# main_xml.net
KiCad netlist of a schematic drawn in EAGLE
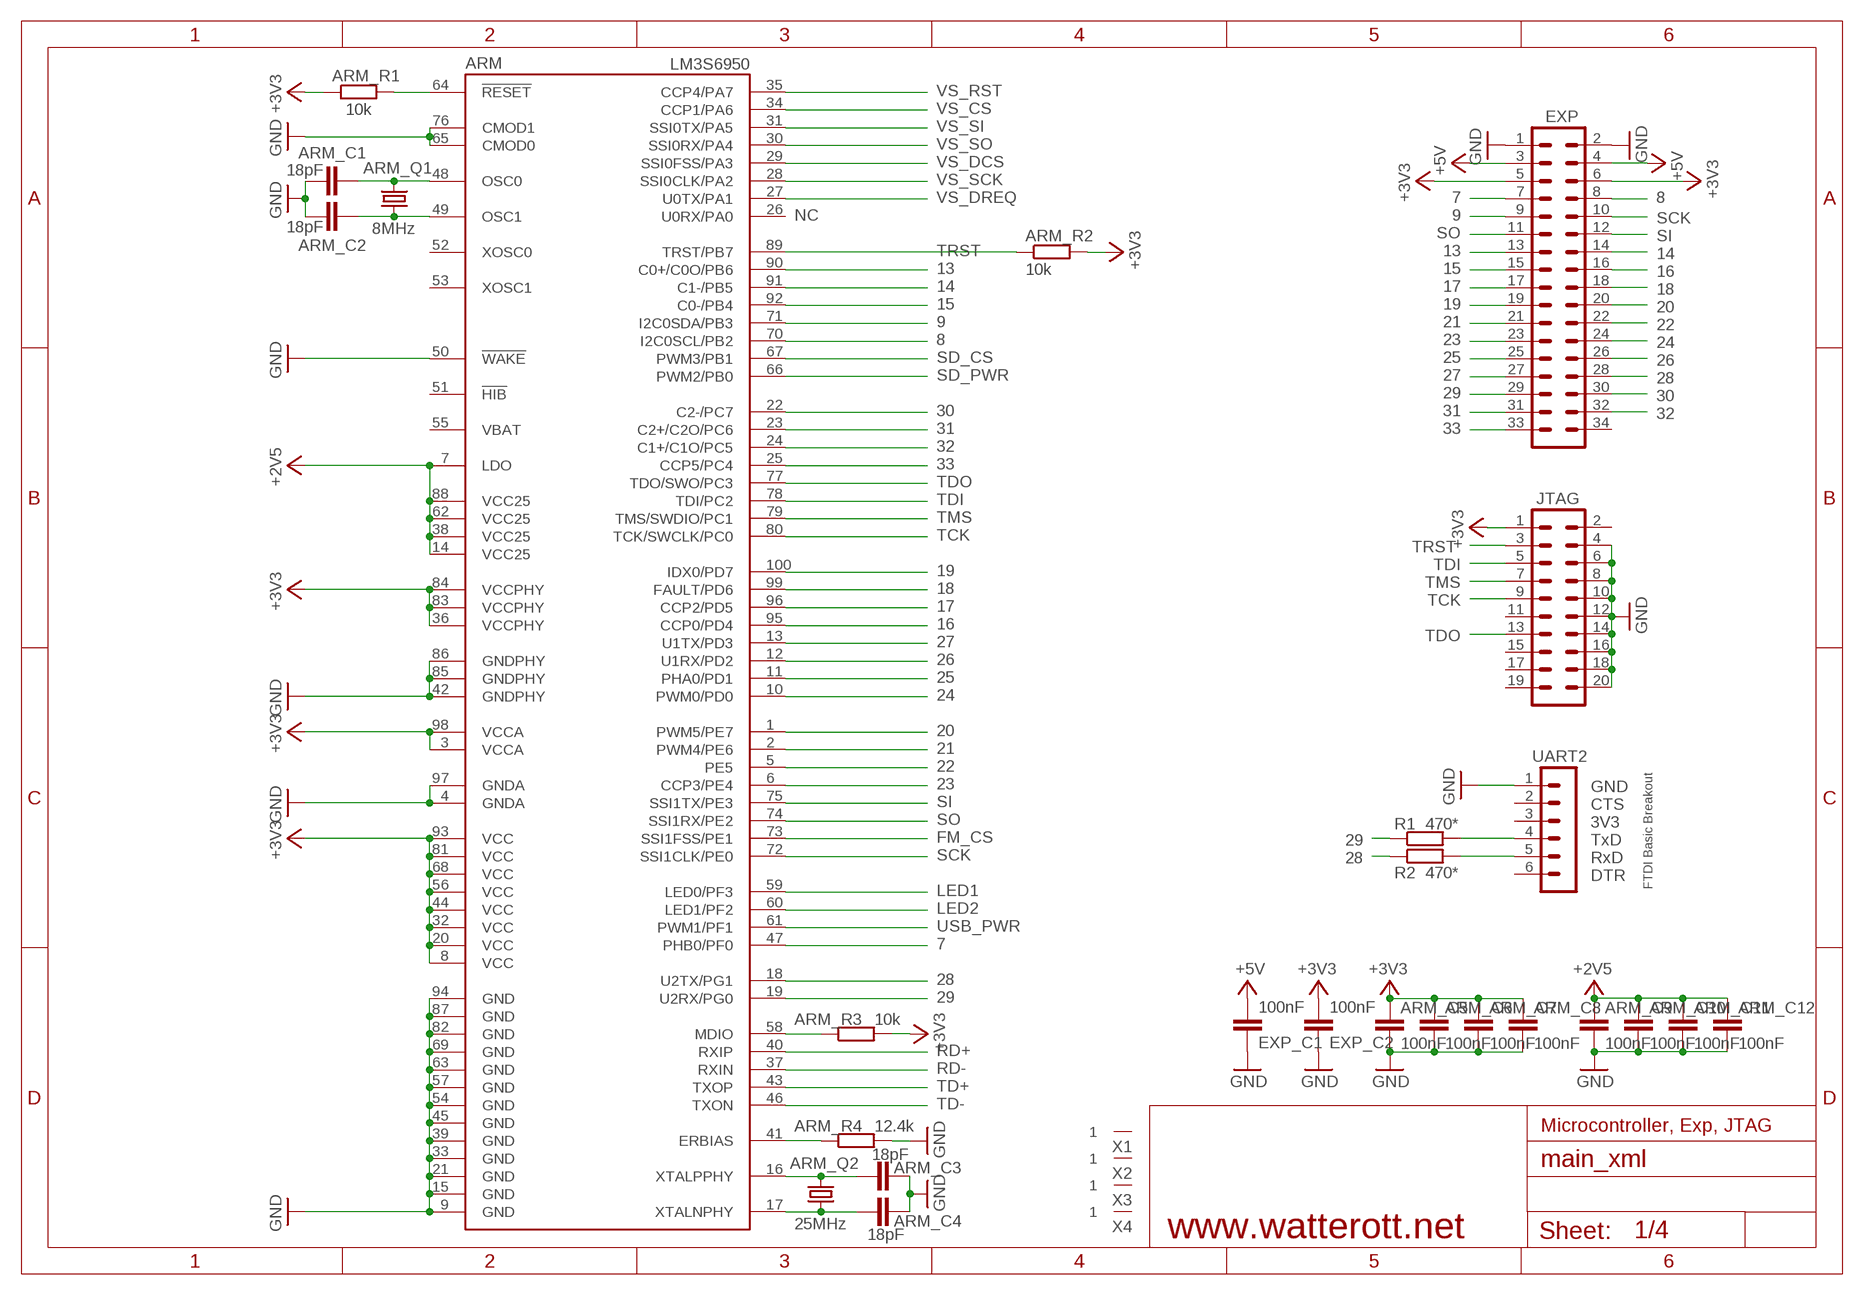
[diagram p0: schematic, sheet 1]
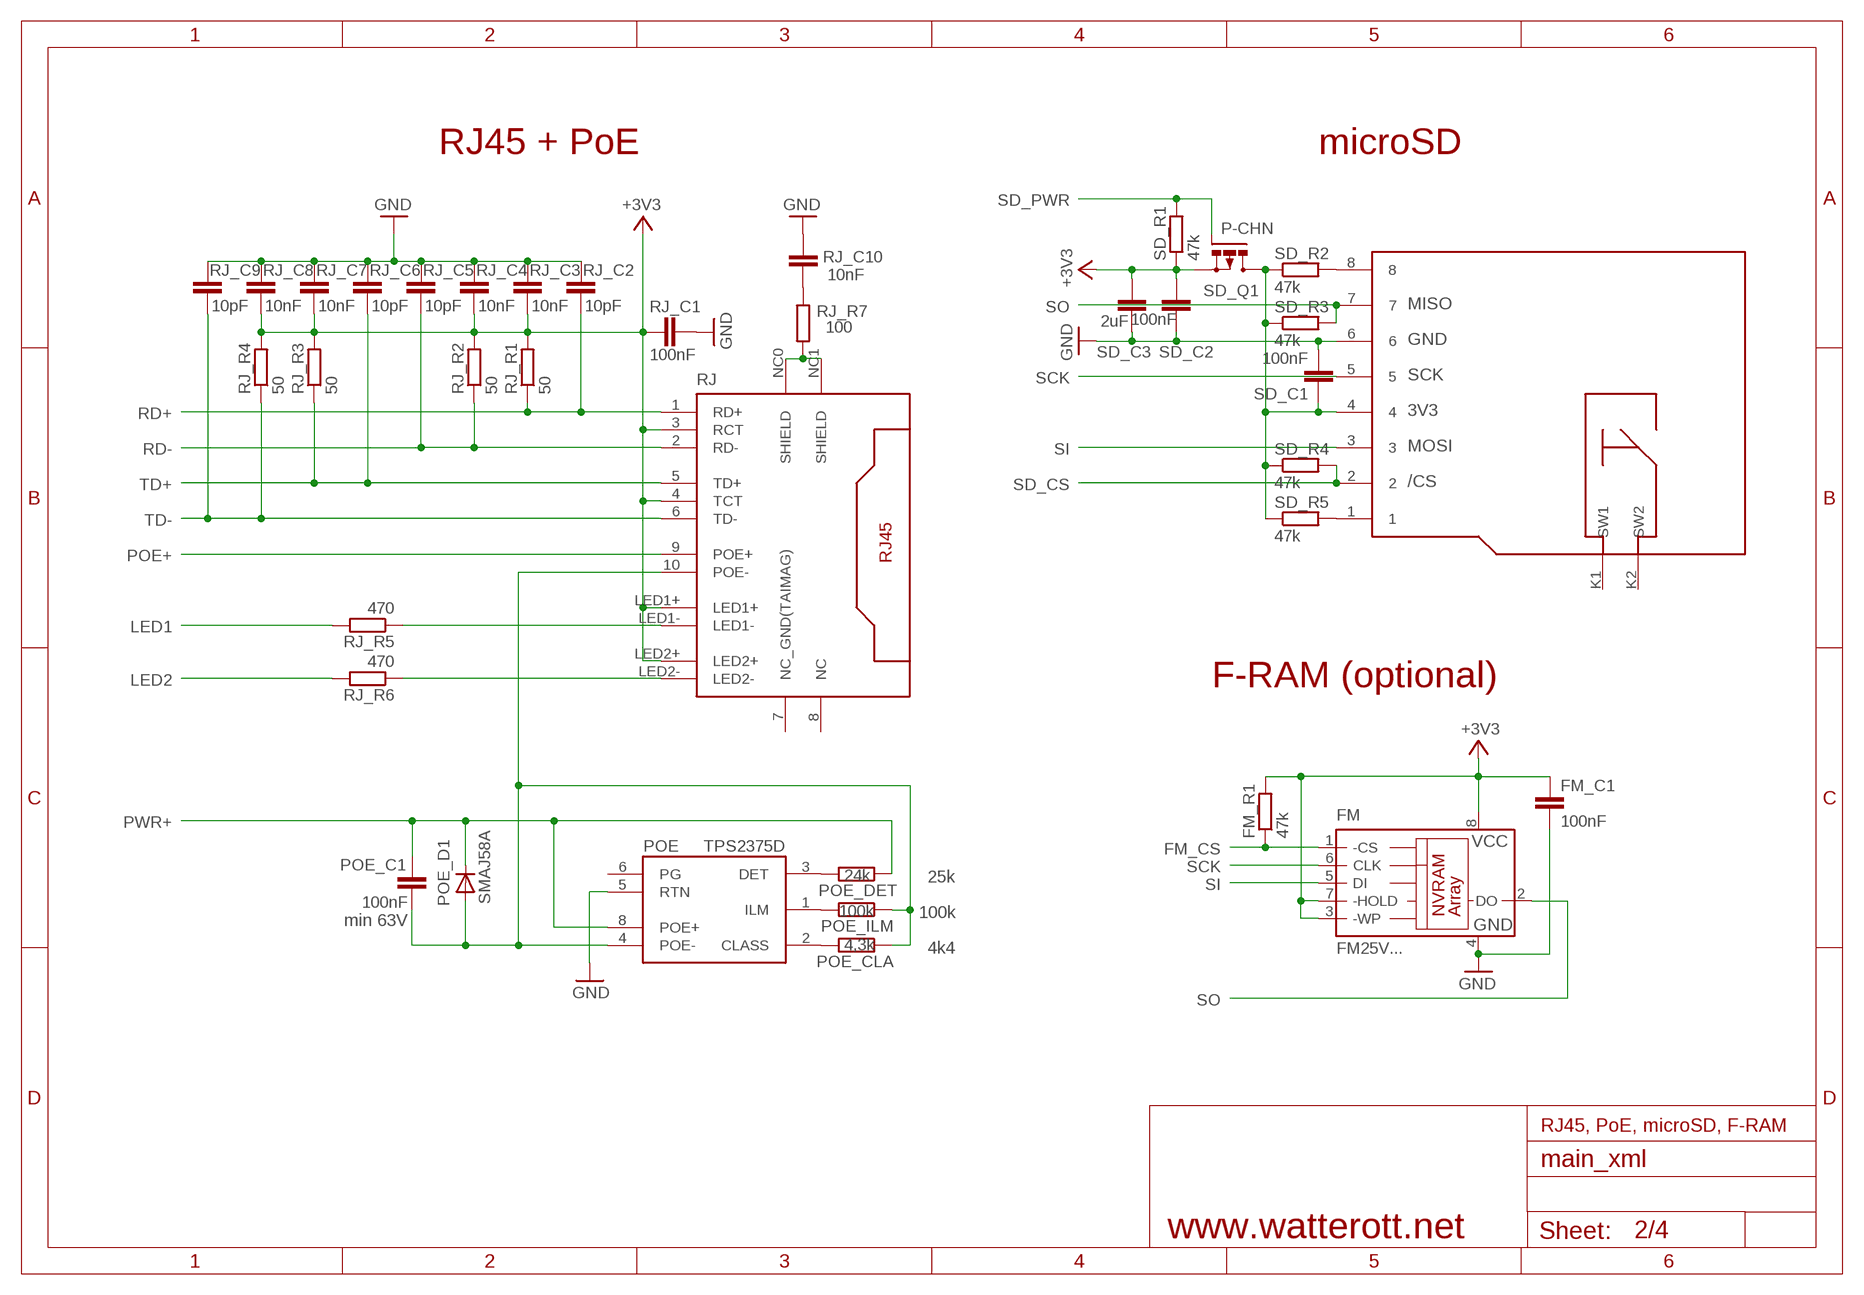
[diagram p1: schematic, sheet 2]
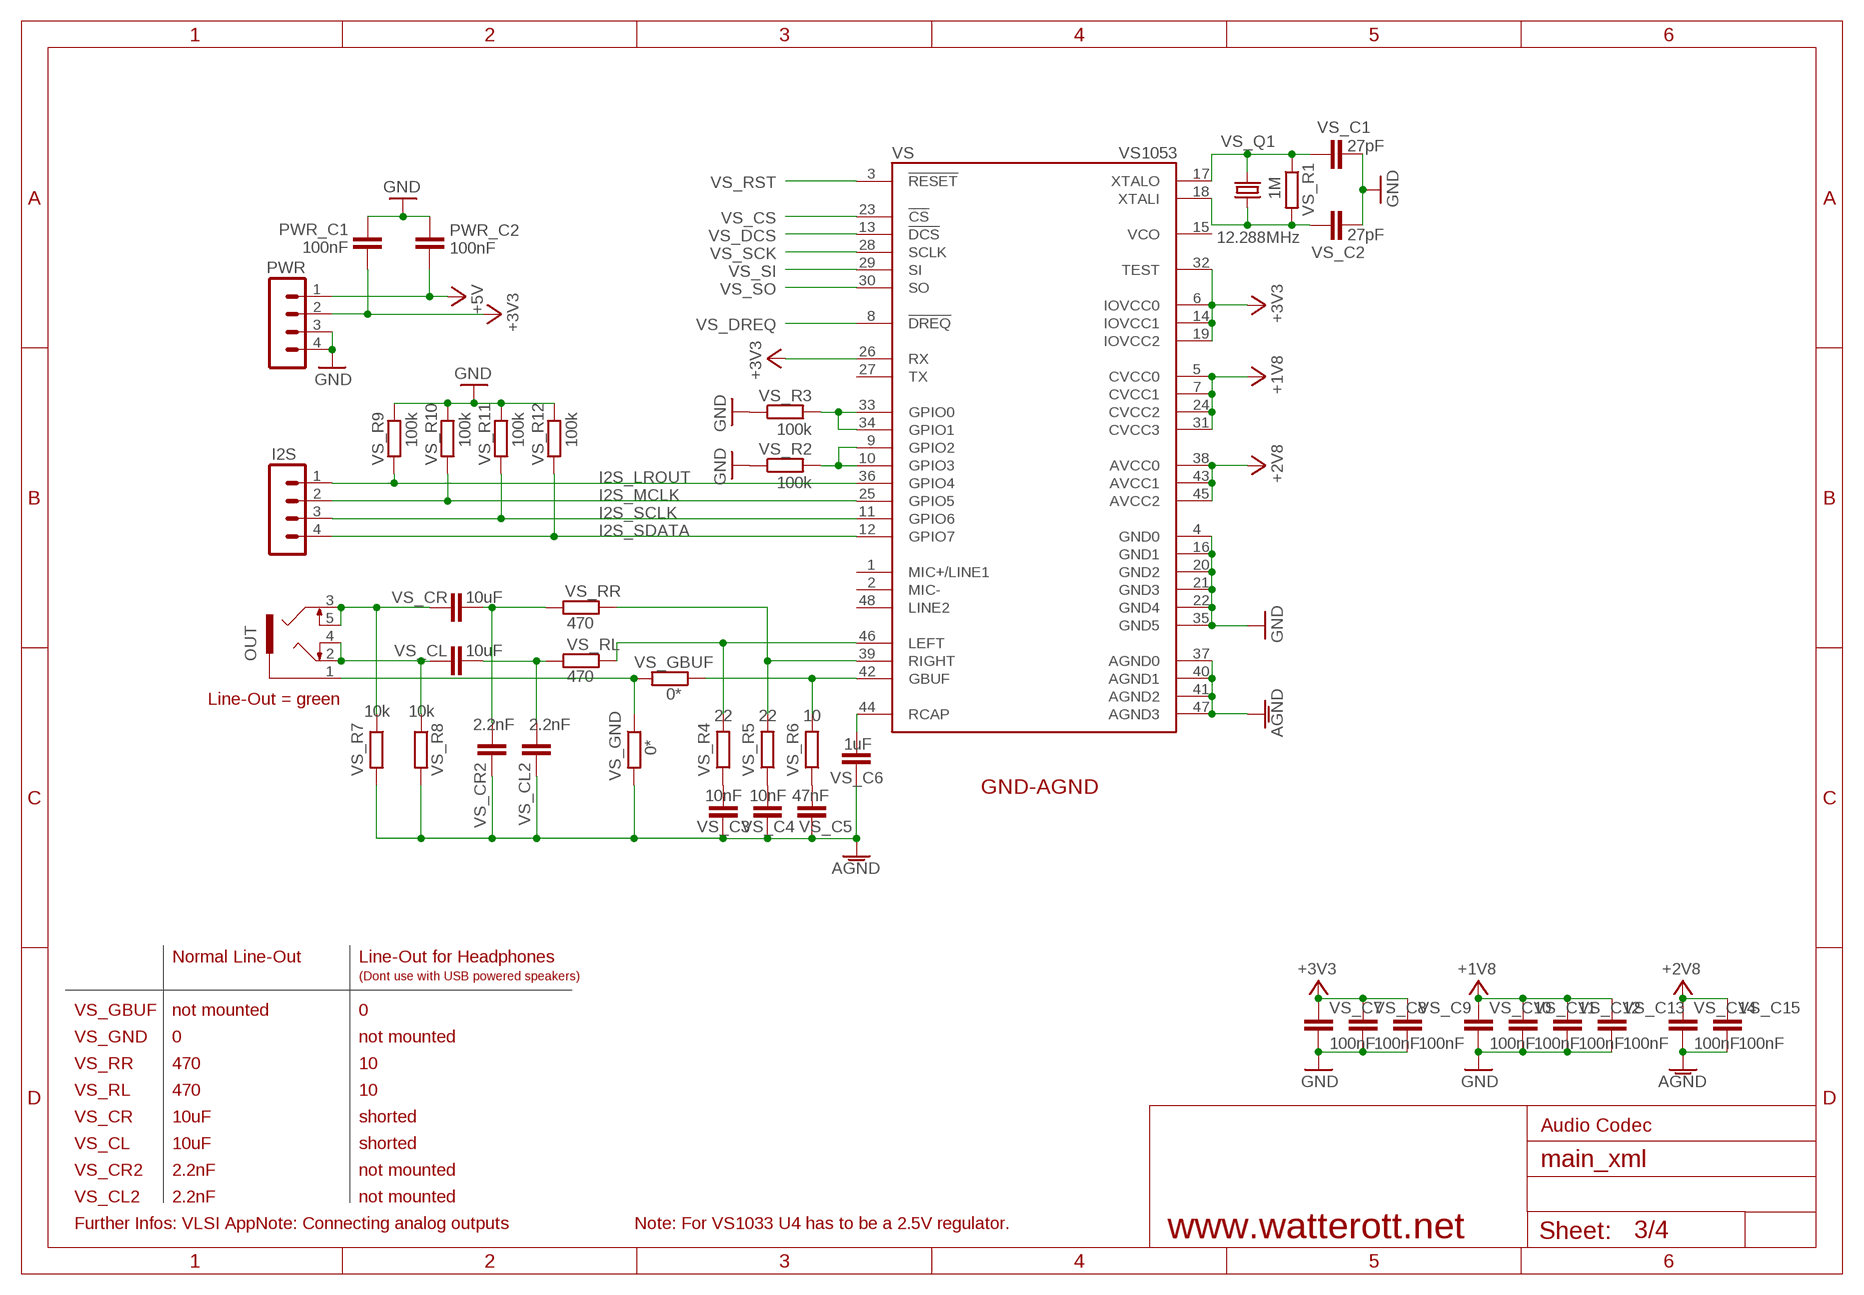
[diagram p2: schematic, sheet 3]
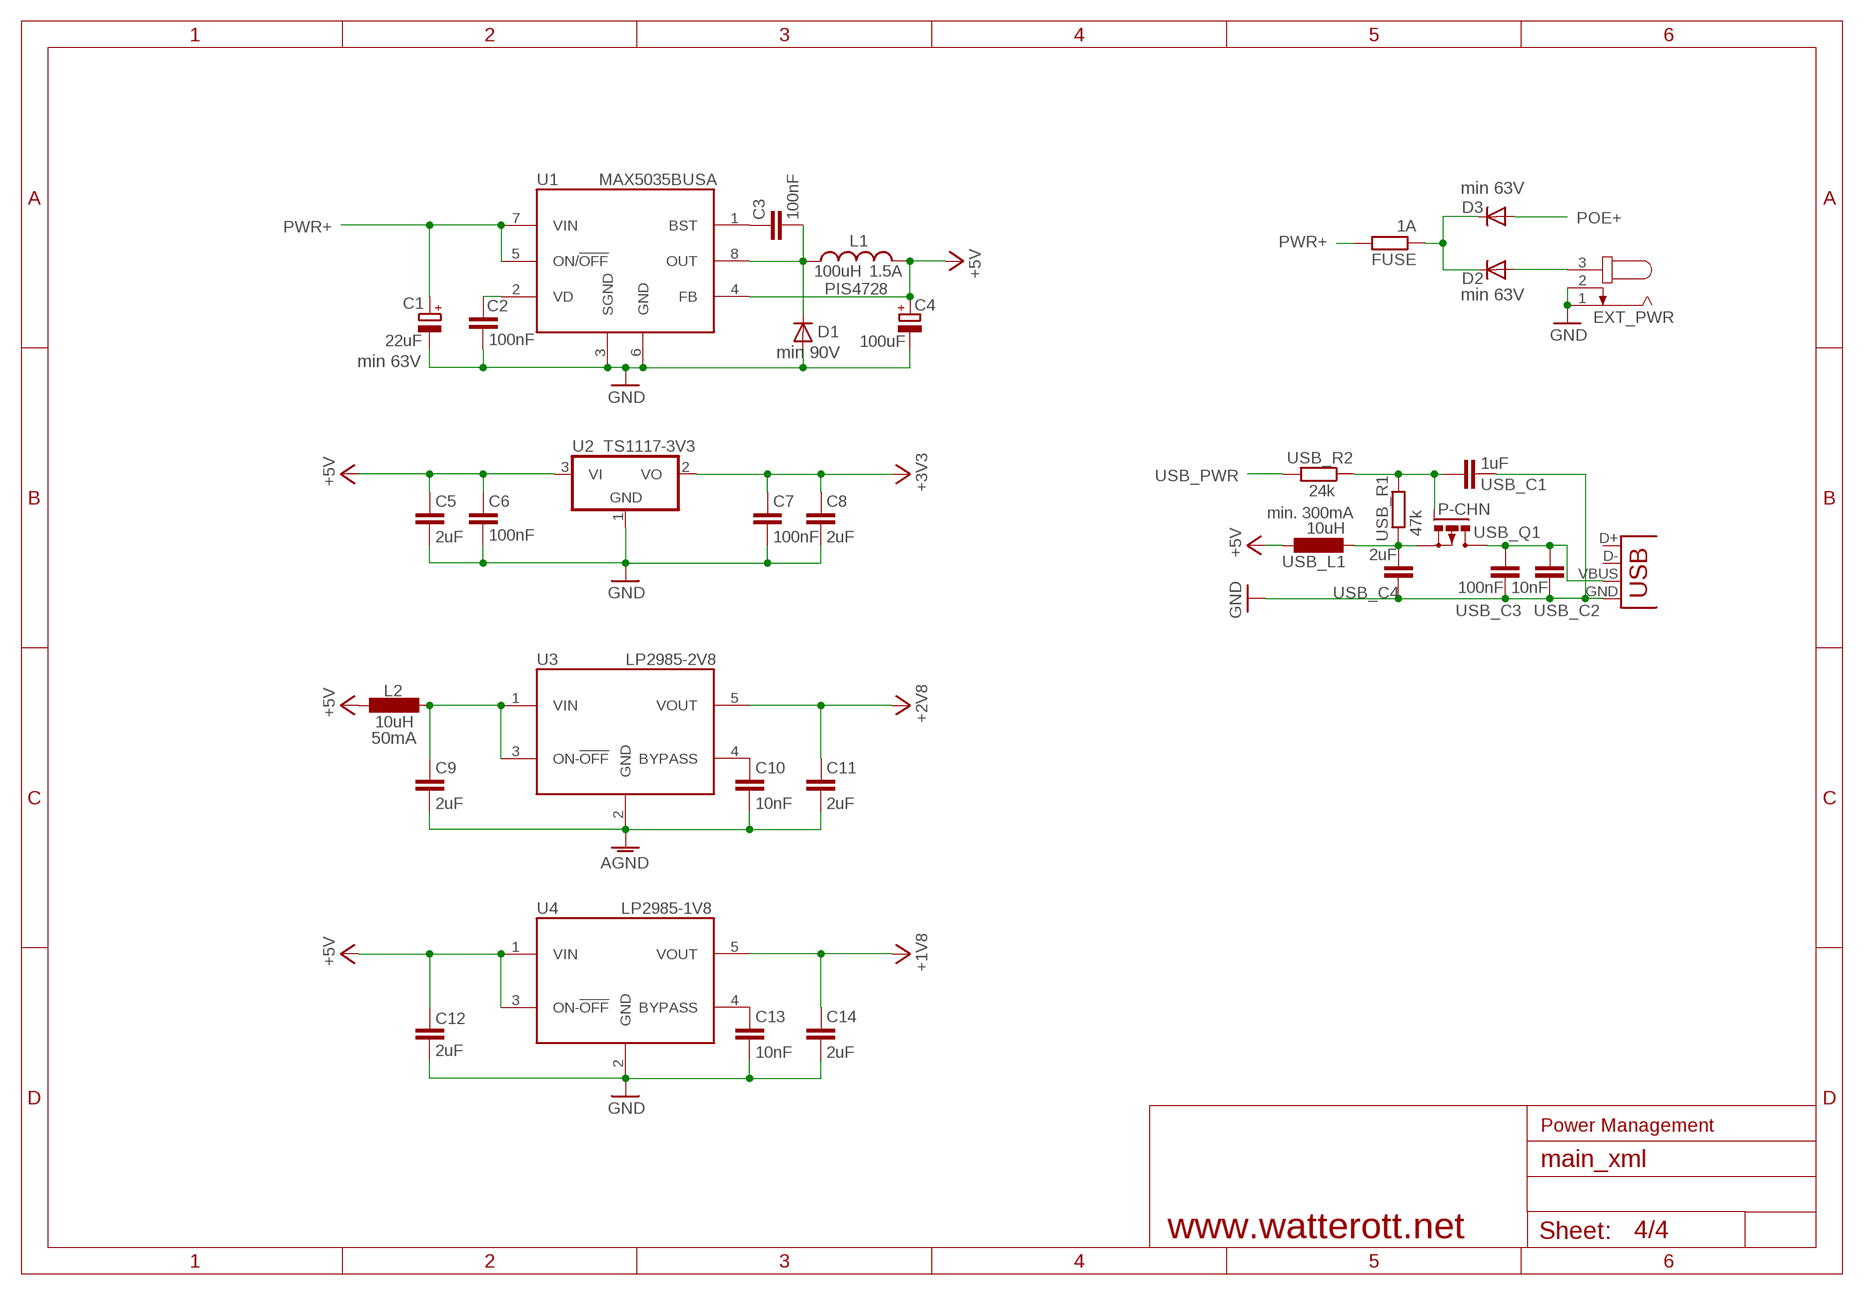
[diagram p3: schematic, sheet 4]

(export (version "E")
  (design (tool "Eeschema 10.0.6"))
  (components
    (comp (ref "I2S")
      (value "MA04-1")
      (footprint "eagle-import:MA04-1")
      (libsource (lib "eagle-import") (part "MA04-1"))
    )
    (comp (ref "OUT")
      (value "1503_09")
      (footprint "eagle-import:1503_09")
      (libsource (lib "eagle-import") (part "1503_09"))
    )
    (comp (ref "PWR")
      (value "MA04-1")
      (footprint "eagle-import:MA04-1")
      (libsource (lib "eagle-import") (part "MA04-1"))
    )
    (comp (ref "PWR_C1")
      (value "100nF")
      (footprint "eagle-import:C0603")
      (libsource (lib "eagle-import") (part "C-EUC0603"))
    )
    (comp (ref "PWR_C2")
      (value "100nF")
      (footprint "eagle-import:C0603")
      (libsource (lib "eagle-import") (part "C-EUC0603"))
    )
    (comp (ref "VS")
      (value "VS1053")
      (footprint "eagle-import:LQFP-48")
      (libsource (lib "eagle-import") (part "VS1053"))
    )
    (comp (ref "VS_C1")
      (value "27pF")
      (footprint "eagle-import:C0603")
      (libsource (lib "eagle-import") (part "C-EUC0603"))
    )
    (comp (ref "VS_C2")
      (value "27pF")
      (footprint "eagle-import:C0603")
      (libsource (lib "eagle-import") (part "C-EUC0603"))
    )
    (comp (ref "VS_C3")
      (value "10nF")
      (footprint "eagle-import:C0603")
      (libsource (lib "eagle-import") (part "C-EUC0603"))
    )
    (comp (ref "VS_C4")
      (value "10nF")
      (footprint "eagle-import:C0603")
      (libsource (lib "eagle-import") (part "C-EUC0603"))
    )
    (comp (ref "VS_C5")
      (value "47nF")
      (footprint "eagle-import:C0603")
      (libsource (lib "eagle-import") (part "C-EUC0603"))
    )
    (comp (ref "VS_C6")
      (value "1uF")
      (footprint "eagle-import:C0603")
      (libsource (lib "eagle-import") (part "C-EUC0603"))
    )
    (comp (ref "VS_C7")
      (value "100nF")
      (footprint "eagle-import:C0603")
      (libsource (lib "eagle-import") (part "C-EUC0603"))
    )
    (comp (ref "VS_C8")
      (value "100nF")
      (footprint "eagle-import:C0603")
      (libsource (lib "eagle-import") (part "C-EUC0603"))
    )
    (comp (ref "VS_C9")
      (value "100nF")
      (footprint "eagle-import:C0603")
      (libsource (lib "eagle-import") (part "C-EUC0603"))
    )
    (comp (ref "VS_C10")
      (value "100nF")
      (footprint "eagle-import:C0603")
      (libsource (lib "eagle-import") (part "C-EUC0603"))
    )
    (comp (ref "VS_C11")
      (value "100nF")
      (footprint "eagle-import:C0603")
      (libsource (lib "eagle-import") (part "C-EUC0603"))
    )
    (comp (ref "VS_C12")
      (value "100nF")
      (footprint "eagle-import:C0603")
      (libsource (lib "eagle-import") (part "C-EUC0603"))
    )
    (comp (ref "VS_C13")
      (value "100nF")
      (footprint "eagle-import:C0603")
      (libsource (lib "eagle-import") (part "C-EUC0603"))
    )
    (comp (ref "VS_C14")
      (value "100nF")
      (footprint "eagle-import:C0603")
      (libsource (lib "eagle-import") (part "C-EUC0603"))
    )
    (comp (ref "VS_C15")
      (value "100nF")
      (footprint "eagle-import:C0603")
      (libsource (lib "eagle-import") (part "C-EUC0603"))
    )
    (comp (ref "VS_CL")
      (value "10uF")
      (footprint "eagle-import:C1210")
      (libsource (lib "eagle-import") (part "C-EUC1210"))
    )
    (comp (ref "VS_CL2")
      (value "2.2nF")
      (footprint "eagle-import:C0603")
      (libsource (lib "eagle-import") (part "C-EUC0603"))
    )
    (comp (ref "VS_CR")
      (value "10uF")
      (footprint "eagle-import:C1210")
      (libsource (lib "eagle-import") (part "C-EUC1210"))
    )
    (comp (ref "VS_CR2")
      (value "2.2nF")
      (footprint "eagle-import:C0603")
      (libsource (lib "eagle-import") (part "C-EUC0603"))
    )
    (comp (ref "VS_GBUF")
      (value "0*")
      (footprint "eagle-import:R0603")
      (libsource (lib "eagle-import") (part "R-EU_R0603"))
    )
    (comp (ref "VS_GND")
      (value "0*")
      (footprint "eagle-import:R0603")
      (libsource (lib "eagle-import") (part "R-EU_R0603"))
    )
    (comp (ref "VS_Q1")
      (value "12.288MHz")
      (footprint "eagle-import:SM49")
      (libsource (lib "eagle-import") (part "CRYSTALSM49"))
    )
    (comp (ref "VS_R1")
      (value "1M")
      (footprint "eagle-import:R0603")
      (libsource (lib "eagle-import") (part "R-EU_R0603"))
    )
    (comp (ref "VS_R2")
      (value "100k")
      (footprint "eagle-import:R0603")
      (libsource (lib "eagle-import") (part "R-EU_R0603"))
    )
    (comp (ref "VS_R3")
      (value "100k")
      (footprint "eagle-import:R0603")
      (libsource (lib "eagle-import") (part "R-EU_R0603"))
    )
    (comp (ref "VS_R4")
      (value "22")
      (footprint "eagle-import:R0603")
      (libsource (lib "eagle-import") (part "R-EU_R0603"))
    )
    (comp (ref "VS_R5")
      (value "22")
      (footprint "eagle-import:R0603")
      (libsource (lib "eagle-import") (part "R-EU_R0603"))
    )
    (comp (ref "VS_R6")
      (value "10")
      (footprint "eagle-import:R0603")
      (libsource (lib "eagle-import") (part "R-EU_R0603"))
    )
    (comp (ref "VS_R7")
      (value "10k")
      (footprint "eagle-import:R0603")
      (libsource (lib "eagle-import") (part "R-EU_R0603"))
    )
    (comp (ref "VS_R8")
      (value "10k")
      (footprint "eagle-import:R0603")
      (libsource (lib "eagle-import") (part "R-EU_R0603"))
    )
    (comp (ref "VS_R9")
      (value "100k")
      (footprint "eagle-import:R0603")
      (libsource (lib "eagle-import") (part "R-EU_R0603"))
    )
    (comp (ref "VS_R10")
      (value "100k")
      (footprint "eagle-import:R0603")
      (libsource (lib "eagle-import") (part "R-EU_R0603"))
    )
    (comp (ref "VS_R11")
      (value "100k")
      (footprint "eagle-import:R0603")
      (libsource (lib "eagle-import") (part "R-EU_R0603"))
    )
    (comp (ref "VS_R12")
      (value "100k")
      (footprint "eagle-import:R0603")
      (libsource (lib "eagle-import") (part "R-EU_R0603"))
    )
    (comp (ref "VS_RL")
      (value "470")
      (footprint "eagle-import:R0603")
      (libsource (lib "eagle-import") (part "R-EU_R0603"))
    )
    (comp (ref "VS_RR")
      (value "470")
      (footprint "eagle-import:R0603")
      (libsource (lib "eagle-import") (part "R-EU_R0603"))
    )
    (comp (ref "FM")
      (value "FM25V...")
      (footprint "eagle-import:SO8")
      (libsource (lib "eagle-import") (part "FM25-S"))
    )
    (comp (ref "FM_C1")
      (value "100nF")
      (footprint "eagle-import:C0603")
      (libsource (lib "eagle-import") (part "C-EUC0603"))
    )
    (comp (ref "FM_R1")
      (value "47k")
      (footprint "eagle-import:R0603")
      (libsource (lib "eagle-import") (part "R-EU_R0603"))
    )
    (comp (ref "POE")
      (value "TPS2375D")
      (footprint "eagle-import:SO08")
      (libsource (lib "eagle-import") (part "TPS237X"))
    )
    (comp (ref "POE_C1")
      (value "100nF")
      (footprint "eagle-import:C1206")
      (fields (field (name "VOLTAGE") "min 63V"))
      (libsource (lib "eagle-import") (part "C-EUC1206"))
    )
    (comp (ref "POE_CLA")
      (value "4,3k")
      (footprint "eagle-import:R0603")
      (libsource (lib "eagle-import") (part "R-EU_R0603"))
    )
    (comp (ref "POE_D1")
      (value "SMAJ58A")
      (footprint "eagle-import:DO214AA")
      (libsource (lib "eagle-import") (part "DIODE-DO214AA"))
    )
    (comp (ref "POE_DET")
      (value "24k")
      (footprint "eagle-import:R0603")
      (libsource (lib "eagle-import") (part "R-EU_R0603"))
    )
    (comp (ref "POE_ILM")
      (value "100k")
      (footprint "eagle-import:R0603")
      (libsource (lib "eagle-import") (part "R-EU_R0603"))
    )
    (comp (ref "RJ")
      (value "RJ45-8-POEWE")
      (footprint "eagle-import:WE_POE")
      (libsource (lib "eagle-import") (part "RJ45-8-POEWE"))
    )
    (comp (ref "RJ_C1")
      (value "100nF")
      (footprint "eagle-import:C0603")
      (libsource (lib "eagle-import") (part "C-EUC0603"))
    )
    (comp (ref "RJ_C2")
      (value "10pF")
      (footprint "eagle-import:C0603")
      (libsource (lib "eagle-import") (part "C-EUC0603"))
    )
    (comp (ref "RJ_C3")
      (value "10nF")
      (footprint "eagle-import:C0603")
      (libsource (lib "eagle-import") (part "C-EUC0603"))
    )
    (comp (ref "RJ_C4")
      (value "10nF")
      (footprint "eagle-import:C0603")
      (libsource (lib "eagle-import") (part "C-EUC0603"))
    )
    (comp (ref "RJ_C5")
      (value "10pF")
      (footprint "eagle-import:C0603")
      (libsource (lib "eagle-import") (part "C-EUC0603"))
    )
    (comp (ref "RJ_C6")
      (value "10pF")
      (footprint "eagle-import:C0603")
      (libsource (lib "eagle-import") (part "C-EUC0603"))
    )
    (comp (ref "RJ_C7")
      (value "10nF")
      (footprint "eagle-import:C0603")
      (libsource (lib "eagle-import") (part "C-EUC0603"))
    )
    (comp (ref "RJ_C8")
      (value "10nF")
      (footprint "eagle-import:C0603")
      (libsource (lib "eagle-import") (part "C-EUC0603"))
    )
    (comp (ref "RJ_C9")
      (value "10pF")
      (footprint "eagle-import:C0603")
      (libsource (lib "eagle-import") (part "C-EUC0603"))
    )
    (comp (ref "RJ_C10")
      (value "10nF")
      (footprint "eagle-import:C0603")
      (libsource (lib "eagle-import") (part "C-EUC0603"))
    )
    (comp (ref "RJ_R1")
      (value "50")
      (footprint "eagle-import:R0603")
      (libsource (lib "eagle-import") (part "R-EU_R0603"))
    )
    (comp (ref "RJ_R2")
      (value "50")
      (footprint "eagle-import:R0603")
      (libsource (lib "eagle-import") (part "R-EU_R0603"))
    )
    (comp (ref "RJ_R3")
      (value "50")
      (footprint "eagle-import:R0603")
      (libsource (lib "eagle-import") (part "R-EU_R0603"))
    )
    (comp (ref "RJ_R4")
      (value "50")
      (footprint "eagle-import:R0603")
      (libsource (lib "eagle-import") (part "R-EU_R0603"))
    )
    (comp (ref "RJ_R5")
      (value "470")
      (footprint "eagle-import:R0603")
      (libsource (lib "eagle-import") (part "R-EU_R0603"))
    )
    (comp (ref "RJ_R6")
      (value "470")
      (footprint "eagle-import:R0603")
      (libsource (lib "eagle-import") (part "R-EU_R0603"))
    )
    (comp (ref "RJ_R7")
      (value "100")
      (footprint "eagle-import:R0603")
      (libsource (lib "eagle-import") (part "R-EU_R0603"))
    )
    (comp (ref "SD")
      (value "MICRO-SD")
      (footprint "eagle-import:MICRO-SD")
      (libsource (lib "eagle-import") (part "MICRO-SD"))
    )
    (comp (ref "SD_C1")
      (value "100nF")
      (footprint "eagle-import:C0603")
      (libsource (lib "eagle-import") (part "C-EUC0603"))
    )
    (comp (ref "SD_C2")
      (value "100nF")
      (footprint "eagle-import:C0603")
      (libsource (lib "eagle-import") (part "C-EUC0603"))
    )
    (comp (ref "SD_C3")
      (value "2uF")
      (footprint "eagle-import:C0603")
      (libsource (lib "eagle-import") (part "C-EUC0603"))
    )
    (comp (ref "SD_Q1")
      (value "P-CHN")
      (footprint "eagle-import:MICRO3")
      (libsource (lib "eagle-import") (part "IRLML6402"))
    )
    (comp (ref "SD_R1")
      (value "47k")
      (footprint "eagle-import:R0603")
      (libsource (lib "eagle-import") (part "R-EU_R0603"))
    )
    (comp (ref "SD_R2")
      (value "47k")
      (footprint "eagle-import:R0603")
      (libsource (lib "eagle-import") (part "R-EU_R0603"))
    )
    (comp (ref "SD_R3")
      (value "47k")
      (footprint "eagle-import:R0603")
      (libsource (lib "eagle-import") (part "R-EU_R0603"))
    )
    (comp (ref "SD_R4")
      (value "47k")
      (footprint "eagle-import:R0603")
      (libsource (lib "eagle-import") (part "R-EU_R0603"))
    )
    (comp (ref "SD_R5")
      (value "47k")
      (footprint "eagle-import:R0603")
      (libsource (lib "eagle-import") (part "R-EU_R0603"))
    )
    (comp (ref "ARM")
      (value "LM3S6950")
      (footprint "eagle-import:LQFP100")
      (libsource (lib "eagle-import") (part "LM3S6950"))
    )
    (comp (ref "ARM_C1")
      (value "18pF")
      (footprint "eagle-import:C0603")
      (libsource (lib "eagle-import") (part "C-EUC0603"))
    )
    (comp (ref "ARM_C2")
      (value "18pF")
      (footprint "eagle-import:C0603")
      (libsource (lib "eagle-import") (part "C-EUC0603"))
    )
    (comp (ref "ARM_C3")
      (value "18pF")
      (footprint "eagle-import:C0603")
      (libsource (lib "eagle-import") (part "C-EUC0603"))
    )
    (comp (ref "ARM_C4")
      (value "18pF")
      (footprint "eagle-import:C0603")
      (libsource (lib "eagle-import") (part "C-EUC0603"))
    )
    (comp (ref "ARM_C5")
      (value "100nF")
      (footprint "eagle-import:C0603")
      (libsource (lib "eagle-import") (part "C-EUC0603"))
    )
    (comp (ref "ARM_C6")
      (value "100nF")
      (footprint "eagle-import:C0603")
      (libsource (lib "eagle-import") (part "C-EUC0603"))
    )
    (comp (ref "ARM_C7")
      (value "100nF")
      (footprint "eagle-import:C0603")
      (libsource (lib "eagle-import") (part "C-EUC0603"))
    )
    (comp (ref "ARM_C8")
      (value "100nF")
      (footprint "eagle-import:C0603")
      (libsource (lib "eagle-import") (part "C-EUC0603"))
    )
    (comp (ref "ARM_C9")
      (value "100nF")
      (footprint "eagle-import:C0603")
      (libsource (lib "eagle-import") (part "C-EUC0603"))
    )
    (comp (ref "ARM_C10")
      (value "100nF")
      (footprint "eagle-import:C0603")
      (libsource (lib "eagle-import") (part "C-EUC0603"))
    )
    (comp (ref "ARM_C11")
      (value "100nF")
      (footprint "eagle-import:C0603")
      (libsource (lib "eagle-import") (part "C-EUC0603"))
    )
    (comp (ref "ARM_C12")
      (value "100nF")
      (footprint "eagle-import:C0603")
      (libsource (lib "eagle-import") (part "C-EUC0603"))
    )
    (comp (ref "ARM_Q1")
      (value "8MHz")
      (footprint "eagle-import:CS10")
      (libsource (lib "eagle-import") (part "CRYSTALCS10"))
    )
    (comp (ref "ARM_Q2")
      (value "25MHz")
      (footprint "eagle-import:CS10")
      (libsource (lib "eagle-import") (part "CRYSTALCS10"))
    )
    (comp (ref "ARM_R1")
      (value "10k")
      (footprint "eagle-import:R0603")
      (libsource (lib "eagle-import") (part "R-EU_R0603"))
    )
    (comp (ref "ARM_R2")
      (value "10k")
      (footprint "eagle-import:R0603")
      (libsource (lib "eagle-import") (part "R-EU_R0603"))
    )
    (comp (ref "ARM_R3")
      (value "10k")
      (footprint "eagle-import:R0603")
      (libsource (lib "eagle-import") (part "R-EU_R0603"))
    )
    (comp (ref "ARM_R4")
      (value "12.4k")
      (footprint "eagle-import:R0603")
      (libsource (lib "eagle-import") (part "R-EU_R0603"))
    )
    (comp (ref "EXP")
      (value "MA17-2")
      (footprint "eagle-import:MA17-2")
      (libsource (lib "eagle-import") (part "MA17-2"))
    )
    (comp (ref "EXP_C1")
      (value "100nF")
      (footprint "eagle-import:C0603")
      (libsource (lib "eagle-import") (part "C-EUC0603"))
    )
    (comp (ref "EXP_C2")
      (value "100nF")
      (footprint "eagle-import:C0603")
      (libsource (lib "eagle-import") (part "C-EUC0603"))
    )
    (comp (ref "JTAG")
      (value "MA10-2SMD")
      (footprint "eagle-import:MA10-2_SMD")
      (libsource (lib "eagle-import") (part "MA10-2SMD"))
    )
    (comp (ref "R1")
      (value "470*")
      (footprint "eagle-import:R0603")
      (libsource (lib "eagle-import") (part "R-EU_R0603"))
    )
    (comp (ref "R2")
      (value "470*")
      (footprint "eagle-import:R0603")
      (libsource (lib "eagle-import") (part "R-EU_R0603"))
    )
    (comp (ref "UART2")
      (value "MA06-1")
      (footprint "eagle-import:MA06-1")
      (libsource (lib "eagle-import") (part "MA06-1"))
    )
    (comp (ref "X1")
      (value "ELLIPTICAL-PADS")
      (footprint "eagle-import:SMD-ELLIPSE")
      (libsource (lib "eagle-import") (part "ELLIPTICAL-PADS"))
    )
    (comp (ref "X2")
      (value "ELLIPTICAL-PADS")
      (footprint "eagle-import:SMD-ELLIPSE")
      (libsource (lib "eagle-import") (part "ELLIPTICAL-PADS"))
    )
    (comp (ref "X3")
      (value "ELLIPTICAL-PADS")
      (footprint "eagle-import:SMD-ELLIPSE")
      (libsource (lib "eagle-import") (part "ELLIPTICAL-PADS"))
    )
    (comp (ref "X4")
      (value "ELLIPTICAL-PADS")
      (footprint "eagle-import:SMD-ELLIPSE")
      (libsource (lib "eagle-import") (part "ELLIPTICAL-PADS"))
    )
    (comp (ref "C1")
      (value "22uF")
      (footprint "eagle-import:153CLV-0810")
      (fields (field (name "VOLTAGE") "min 63V"))
      (libsource (lib "eagle-import") (part "CPOL-EU153CLV-0810"))
    )
    (comp (ref "C2")
      (value "100nF")
      (footprint "eagle-import:C0603")
      (libsource (lib "eagle-import") (part "C-EUC0603"))
    )
    (comp (ref "C3")
      (value "100nF")
      (footprint "eagle-import:C0603")
      (libsource (lib "eagle-import") (part "C-EUC0603"))
    )
    (comp (ref "C4")
      (value "100uF")
      (footprint "eagle-import:153CLV-0810")
      (libsource (lib "eagle-import") (part "CPOL-EU153CLV-0810"))
    )
    (comp (ref "C5")
      (value "2uF")
      (footprint "eagle-import:C0603")
      (libsource (lib "eagle-import") (part "C-EUC0603"))
    )
    (comp (ref "C6")
      (value "100nF")
      (footprint "eagle-import:C0603")
      (libsource (lib "eagle-import") (part "C-EUC0603"))
    )
    (comp (ref "C7")
      (value "100nF")
      (footprint "eagle-import:C0603")
      (libsource (lib "eagle-import") (part "C-EUC0603"))
    )
    (comp (ref "C8")
      (value "2uF")
      (footprint "eagle-import:C0603")
      (libsource (lib "eagle-import") (part "C-EUC0603"))
    )
    (comp (ref "C9")
      (value "2uF")
      (footprint "eagle-import:C0603")
      (libsource (lib "eagle-import") (part "C-EUC0603"))
    )
    (comp (ref "C10")
      (value "10nF")
      (footprint "eagle-import:C0603")
      (libsource (lib "eagle-import") (part "C-EUC0603"))
    )
    (comp (ref "C11")
      (value "2uF")
      (footprint "eagle-import:C0603")
      (libsource (lib "eagle-import") (part "C-EUC0603"))
    )
    (comp (ref "C12")
      (value "2uF")
      (footprint "eagle-import:C0603")
      (libsource (lib "eagle-import") (part "C-EUC0603"))
    )
    (comp (ref "C13")
      (value "10nF")
      (footprint "eagle-import:C0603")
      (libsource (lib "eagle-import") (part "C-EUC0603"))
    )
    (comp (ref "C14")
      (value "2uF")
      (footprint "eagle-import:C0603")
      (libsource (lib "eagle-import") (part "C-EUC0603"))
    )
    (comp (ref "D1")
      (value "DIODE-DO214AA")
      (footprint "eagle-import:DO214AA")
      (fields (field (name "VOLTAGE") "min 90V"))
      (libsource (lib "eagle-import") (part "DIODE-DO214AA"))
    )
    (comp (ref "D2")
      (value "DIODE-DO214AA")
      (footprint "eagle-import:DO214AA")
      (fields (field (name "VOLTAGE") "min 63V"))
      (libsource (lib "eagle-import") (part "DIODE-DO214AA"))
    )
    (comp (ref "D3")
      (value "DIODE-DO214AA")
      (footprint "eagle-import:DO214AA")
      (fields (field (name "VOLTAGE") "min 63V"))
      (libsource (lib "eagle-import") (part "DIODE-DO214AA"))
    )
    (comp (ref "EXT_PWR")
      (value "JACK-PLUG0")
      (footprint "eagle-import:SPC4077")
      (libsource (lib "eagle-import") (part "JACK-PLUG0"))
    )
    (comp (ref "FUSE")
      (value "1A")
      (footprint "eagle-import:R1206")
      (libsource (lib "eagle-import") (part "R-EU_R1206"))
    )
    (comp (ref "L1")
      (value "100uH")
      (footprint "eagle-import:CDRH")
      (libsource (lib "eagle-import") (part "INDUCTORCDRH"))
    )
    (comp (ref "L2")
      (value "10uH")
      (footprint "eagle-import:L3230M")
      (fields (field (name "CURRENT") "50mA"))
      (libsource (lib "eagle-import") (part "L-EUL3230M"))
    )
    (comp (ref "U1")
      (value "MAX5035BUSA")
      (footprint "eagle-import:SO8")
      (libsource (lib "eagle-import") (part "MAX5035"))
    )
    (comp (ref "U2")
      (value "TS1117-3V3")
      (footprint "eagle-import:SOT223")
      (libsource (lib "eagle-import") (part "TS1117"))
    )
    (comp (ref "U3")
      (value "LP2985-2V8")
      (footprint "eagle-import:SOT23-5")
      (libsource (lib "eagle-import") (part "LP2985"))
    )
    (comp (ref "U4")
      (value "LP2985-1V8")
      (footprint "eagle-import:SOT23-5")
      (libsource (lib "eagle-import") (part "LP2985"))
    )
    (comp (ref "USB")
      (value "USB-A-S")
      (footprint "eagle-import:USB-A-S")
      (libsource (lib "eagle-import") (part "USB-A-S"))
    )
    (comp (ref "USB_C1")
      (value "1uF")
      (footprint "eagle-import:C0603")
      (libsource (lib "eagle-import") (part "C-EUC0603"))
    )
    (comp (ref "USB_C2")
      (value "10nF")
      (footprint "eagle-import:C0603")
      (libsource (lib "eagle-import") (part "C-EUC0603"))
    )
    (comp (ref "USB_C3")
      (value "100nF")
      (footprint "eagle-import:C0603")
      (libsource (lib "eagle-import") (part "C-EUC0603"))
    )
    (comp (ref "USB_C4")
      (value "2uF")
      (footprint "eagle-import:C0805")
      (libsource (lib "eagle-import") (part "C-EUC0805"))
    )
    (comp (ref "USB_L1")
      (value "10uH")
      (footprint "eagle-import:L3230M")
      (fields (field (name "CURRENT") "min. 300mA"))
      (libsource (lib "eagle-import") (part "L-EUL3230M"))
    )
    (comp (ref "USB_Q1")
      (value "P-CHN")
      (footprint "eagle-import:MICRO3")
      (libsource (lib "eagle-import") (part "IRLML6402"))
    )
    (comp (ref "USB_R1")
      (value "47k")
      (footprint "eagle-import:R0603")
      (libsource (lib "eagle-import") (part "R-EU_R0603"))
    )
    (comp (ref "USB_R2")
      (value "24k")
      (footprint "eagle-import:R0603")
      (libsource (lib "eagle-import") (part "R-EU_R0603"))
    )
  )
  (nets
    (net (code "1") (name "+1V8") (class "Default")
      (node (ref "C14") (pin "1") (pinfunction "1_1") (pintype "passive"))
      (node (ref "U4") (pin "5") (pinfunction "VOUT_5") (pintype "power_in"))
      (node (ref "VS") (pin "24") (pinfunction "CVCC2_24") (pintype "power_in"))
      (node (ref "VS") (pin "31") (pinfunction "CVCC3_31") (pintype "power_in"))
      (node (ref "VS") (pin "5") (pinfunction "CVCC0_5") (pintype "power_in"))
      (node (ref "VS") (pin "7") (pinfunction "CVCC1_7") (pintype "power_in"))
      (node (ref "VS_C10") (pin "1") (pinfunction "1_1") (pintype "passive"))
      (node (ref "VS_C11") (pin "1") (pinfunction "1_1") (pintype "passive"))
      (node (ref "VS_C12") (pin "1") (pinfunction "1_1") (pintype "passive"))
      (node (ref "VS_C13") (pin "1") (pinfunction "1_1") (pintype "passive"))
    )
    (net (code "2") (name "+2V5") (class "Default")
      (node (ref "ARM") (pin "14") (pinfunction "VCC25_14") (pintype "power_in"))
      (node (ref "ARM") (pin "38") (pinfunction "VCC25_38") (pintype "power_in"))
      (node (ref "ARM") (pin "62") (pinfunction "VCC25_62") (pintype "power_in"))
      (node (ref "ARM") (pin "7") (pinfunction "LDO_7") (pintype "power_in"))
      (node (ref "ARM") (pin "88") (pinfunction "VCC25_88") (pintype "power_in"))
      (node (ref "ARM_C10") (pin "1") (pinfunction "1_1") (pintype "passive"))
      (node (ref "ARM_C11") (pin "1") (pinfunction "1_1") (pintype "passive"))
      (node (ref "ARM_C12") (pin "1") (pinfunction "1_1") (pintype "passive"))
      (node (ref "ARM_C9") (pin "1") (pinfunction "1_1") (pintype "passive"))
    )
    (net (code "3") (name "+2V8") (class "Default")
      (node (ref "C11") (pin "1") (pinfunction "1_1") (pintype "passive"))
      (node (ref "U3") (pin "5") (pinfunction "VOUT_5") (pintype "power_in"))
      (node (ref "VS") (pin "38") (pinfunction "AVCC0_38") (pintype "power_in"))
      (node (ref "VS") (pin "43") (pinfunction "AVCC1_43") (pintype "power_in"))
      (node (ref "VS") (pin "45") (pinfunction "AVCC2_45") (pintype "power_in"))
      (node (ref "VS_C14") (pin "1") (pinfunction "1_1") (pintype "passive"))
      (node (ref "VS_C15") (pin "1") (pinfunction "1_1") (pintype "passive"))
    )
    (net (code "4") (name "+3V3") (class "Default")
      (node (ref "ARM") (pin "20") (pinfunction "VCC_20") (pintype "power_in"))
      (node (ref "ARM") (pin "3") (pinfunction "VCCA_3") (pintype "power_in"))
      (node (ref "ARM") (pin "32") (pinfunction "VCC_32") (pintype "power_in"))
      (node (ref "ARM") (pin "36") (pinfunction "VCCPHY_36") (pintype "power_in"))
      (node (ref "ARM") (pin "44") (pinfunction "VCC_44") (pintype "power_in"))
      (node (ref "ARM") (pin "56") (pinfunction "VCC_56") (pintype "power_in"))
      (node (ref "ARM") (pin "68") (pinfunction "VCC_68") (pintype "power_in"))
      (node (ref "ARM") (pin "8") (pinfunction "VCC_8") (pintype "power_in"))
      (node (ref "ARM") (pin "81") (pinfunction "VCC_81") (pintype "power_in"))
      (node (ref "ARM") (pin "83") (pinfunction "VCCPHY_83") (pintype "power_in"))
      (node (ref "ARM") (pin "84") (pinfunction "VCCPHY_84") (pintype "power_in"))
      (node (ref "ARM") (pin "93") (pinfunction "VCC_93") (pintype "power_in"))
      (node (ref "ARM") (pin "98") (pinfunction "VCCA_98") (pintype "power_in"))
      (node (ref "ARM_C5") (pin "1") (pinfunction "1_1") (pintype "passive"))
      (node (ref "ARM_C6") (pin "1") (pinfunction "1_1") (pintype "passive"))
      (node (ref "ARM_C7") (pin "1") (pinfunction "1_1") (pintype "passive"))
      (node (ref "ARM_C8") (pin "1") (pinfunction "1_1") (pintype "passive"))
      (node (ref "ARM_R1") (pin "1") (pinfunction "1_1") (pintype "passive"))
      (node (ref "ARM_R2") (pin "2") (pinfunction "2_2") (pintype "passive"))
      (node (ref "ARM_R3") (pin "2") (pinfunction "2_2") (pintype "passive"))
      (node (ref "C7") (pin "1") (pinfunction "1_1") (pintype "passive"))
      (node (ref "C8") (pin "1") (pinfunction "1_1") (pintype "passive"))
      (node (ref "EXP") (pin "5") (pinfunction "5_5") (pintype "passive"))
      (node (ref "EXP") (pin "6") (pinfunction "6_6") (pintype "passive"))
      (node (ref "EXP_C2") (pin "2") (pinfunction "2_2") (pintype "passive"))
      (node (ref "FM") (pin "3") (pinfunction "-WP_3") (pintype "input"))
      (node (ref "FM") (pin "7") (pinfunction "-HOLD_7") (pintype "input"))
      (node (ref "FM") (pin "8") (pinfunction "VCC_8") (pintype "power_in"))
      (node (ref "FM_C1") (pin "1") (pinfunction "1_1") (pintype "passive"))
      (node (ref "FM_R1") (pin "2") (pinfunction "2_2") (pintype "passive"))
      (node (ref "JTAG") (pin "1") (pinfunction "1_1") (pintype "passive"))
      (node (ref "PWR") (pin "2") (pinfunction "2_2") (pintype "passive"))
      (node (ref "PWR_C1") (pin "2") (pinfunction "2_2") (pintype "passive"))
      (node (ref "RJ") (pin "3") (pinfunction "RCT_3") (pintype "bidirectional"))
      (node (ref "RJ") (pin "4") (pinfunction "TCT_4") (pintype "bidirectional"))
      (node (ref "RJ") (pin "LED1+") (pinfunction "LED1+_LED1+") (pintype "input"))
      (node (ref "RJ") (pin "LED2+") (pinfunction "LED2+_LED2+") (pintype "input"))
      (node (ref "RJ_C1") (pin "1") (pinfunction "1_1") (pintype "passive"))
      (node (ref "RJ_C3") (pin "2") (pinfunction "2_2") (pintype "passive"))
      (node (ref "RJ_C4") (pin "2") (pinfunction "2_2") (pintype "passive"))
      (node (ref "RJ_C7") (pin "2") (pinfunction "2_2") (pintype "passive"))
      (node (ref "RJ_C8") (pin "2") (pinfunction "2_2") (pintype "passive"))
      (node (ref "RJ_R1") (pin "2") (pinfunction "2_2") (pintype "passive"))
      (node (ref "RJ_R2") (pin "2") (pinfunction "2_2") (pintype "passive"))
      (node (ref "RJ_R3") (pin "2") (pinfunction "2_2") (pintype "passive"))
      (node (ref "RJ_R4") (pin "2") (pinfunction "2_2") (pintype "passive"))
      (node (ref "SD_C2") (pin "2") (pinfunction "2_2") (pintype "passive"))
      (node (ref "SD_C3") (pin "2") (pinfunction "2_2") (pintype "passive"))
      (node (ref "SD_Q1") (pin "2") (pinfunction "S_2") (pintype "passive"))
      (node (ref "SD_R1") (pin "1") (pinfunction "1_1") (pintype "passive"))
      (node (ref "U2") (pin "2") (pinfunction "VO_2") (pintype "passive"))
      (node (ref "VS") (pin "14") (pinfunction "IOVCC1_14") (pintype "power_in"))
      (node (ref "VS") (pin "19") (pinfunction "IOVCC2_19") (pintype "power_in"))
      (node (ref "VS") (pin "26") (pinfunction "RX_26") (pintype "input"))
      (node (ref "VS") (pin "32") (pinfunction "TEST_32") (pintype "input"))
      (node (ref "VS") (pin "6") (pinfunction "IOVCC0_6") (pintype "power_in"))
      (node (ref "VS_C7") (pin "1") (pinfunction "1_1") (pintype "passive"))
      (node (ref "VS_C8") (pin "1") (pinfunction "1_1") (pintype "passive"))
      (node (ref "VS_C9") (pin "1") (pinfunction "1_1") (pintype "passive"))
    )
    (net (code "5") (name "+5V") (class "Default")
      (node (ref "C12") (pin "2") (pinfunction "2_2") (pintype "passive"))
      (node (ref "C4") (pin "+") (pinfunction "+_+") (pintype "passive"))
      (node (ref "C5") (pin "1") (pinfunction "1_1") (pintype "passive"))
      (node (ref "C6") (pin "2") (pinfunction "2_2") (pintype "passive"))
      (node (ref "EXP") (pin "3") (pinfunction "3_3") (pintype "passive"))
      (node (ref "EXP") (pin "4") (pinfunction "4_4") (pintype "passive"))
      (node (ref "EXP_C1") (pin "2") (pinfunction "2_2") (pintype "passive"))
      (node (ref "L1") (pin "2") (pinfunction "2_2") (pintype "passive"))
      (node (ref "L2") (pin "1") (pinfunction "1_1") (pintype "passive"))
      (node (ref "PWR") (pin "1") (pinfunction "1_1") (pintype "passive"))
      (node (ref "PWR_C2") (pin "2") (pinfunction "2_2") (pintype "passive"))
      (node (ref "U1") (pin "4") (pinfunction "FB_4") (pintype "input"))
      (node (ref "U2") (pin "3") (pinfunction "VI_3") (pintype "input"))
      (node (ref "U4") (pin "1") (pinfunction "VIN_1") (pintype "power_in"))
      (node (ref "U4") (pin "3") (pinfunction "ON-~{OFF}_3") (pintype "input"))
      (node (ref "USB_L1") (pin "1") (pinfunction "1_1") (pintype "passive"))
    )
    (net (code "6") (name "7") (class "Default")
      (node (ref "ARM") (pin "47") (pinfunction "PHB0/PF0_47") (pintype "bidirectional"))
      (node (ref "EXP") (pin "7") (pinfunction "7_7") (pintype "passive"))
    )
    (net (code "7") (name "8") (class "Default")
      (node (ref "ARM") (pin "70") (pinfunction "I2C0SCL/PB2_70") (pintype "bidirectional"))
      (node (ref "EXP") (pin "8") (pinfunction "8_8") (pintype "passive"))
    )
    (net (code "8") (name "9") (class "Default")
      (node (ref "ARM") (pin "71") (pinfunction "I2C0SDA/PB3_71") (pintype "bidirectional"))
      (node (ref "EXP") (pin "9") (pinfunction "9_9") (pintype "passive"))
    )
    (net (code "9") (name "13") (class "Default")
      (node (ref "ARM") (pin "90") (pinfunction "C0+/C0O/PB6_90") (pintype "bidirectional"))
      (node (ref "EXP") (pin "13") (pinfunction "13_13") (pintype "passive"))
    )
    (net (code "10") (name "14") (class "Default")
      (node (ref "ARM") (pin "91") (pinfunction "C1-/PB5_91") (pintype "bidirectional"))
      (node (ref "EXP") (pin "14") (pinfunction "14_14") (pintype "passive"))
    )
    (net (code "11") (name "15") (class "Default")
      (node (ref "ARM") (pin "92") (pinfunction "C0-/PB4_92") (pintype "bidirectional"))
      (node (ref "EXP") (pin "15") (pinfunction "15_15") (pintype "passive"))
    )
    (net (code "12") (name "16") (class "Default")
      (node (ref "ARM") (pin "95") (pinfunction "CCP0/PD4_95") (pintype "bidirectional"))
      (node (ref "EXP") (pin "16") (pinfunction "16_16") (pintype "passive"))
    )
    (net (code "13") (name "17") (class "Default")
      (node (ref "ARM") (pin "96") (pinfunction "CCP2/PD5_96") (pintype "bidirectional"))
      (node (ref "EXP") (pin "17") (pinfunction "17_17") (pintype "passive"))
    )
    (net (code "14") (name "18") (class "Default")
      (node (ref "ARM") (pin "99") (pinfunction "FAULT/PD6_99") (pintype "bidirectional"))
      (node (ref "EXP") (pin "18") (pinfunction "18_18") (pintype "passive"))
    )
    (net (code "15") (name "19") (class "Default")
      (node (ref "ARM") (pin "100") (pinfunction "IDX0/PD7_100") (pintype "bidirectional"))
      (node (ref "EXP") (pin "19") (pinfunction "19_19") (pintype "passive"))
    )
    (net (code "16") (name "20") (class "Default")
      (node (ref "ARM") (pin "1") (pinfunction "PWM5/PE7_1") (pintype "bidirectional"))
      (node (ref "EXP") (pin "20") (pinfunction "20_20") (pintype "passive"))
    )
    (net (code "17") (name "21") (class "Default")
      (node (ref "ARM") (pin "2") (pinfunction "PWM4/PE6_2") (pintype "bidirectional"))
      (node (ref "EXP") (pin "21") (pinfunction "21_21") (pintype "passive"))
    )
    (net (code "18") (name "22") (class "Default")
      (node (ref "ARM") (pin "5") (pinfunction "PE5_5") (pintype "bidirectional"))
      (node (ref "EXP") (pin "22") (pinfunction "22_22") (pintype "passive"))
    )
    (net (code "19") (name "23") (class "Default")
      (node (ref "ARM") (pin "6") (pinfunction "CCP3/PE4_6") (pintype "bidirectional"))
      (node (ref "EXP") (pin "23") (pinfunction "23_23") (pintype "passive"))
    )
    (net (code "20") (name "24") (class "Default")
      (node (ref "ARM") (pin "10") (pinfunction "PWM0/PD0_10") (pintype "bidirectional"))
      (node (ref "EXP") (pin "24") (pinfunction "24_24") (pintype "passive"))
    )
    (net (code "21") (name "25") (class "Default")
      (node (ref "ARM") (pin "11") (pinfunction "PHA0/PD1_11") (pintype "bidirectional"))
      (node (ref "EXP") (pin "25") (pinfunction "25_25") (pintype "passive"))
    )
    (net (code "22") (name "26") (class "Default")
      (node (ref "ARM") (pin "12") (pinfunction "U1RX/PD2_12") (pintype "bidirectional"))
      (node (ref "EXP") (pin "26") (pinfunction "26_26") (pintype "passive"))
    )
    (net (code "23") (name "27") (class "Default")
      (node (ref "ARM") (pin "13") (pinfunction "U1TX/PD3_13") (pintype "bidirectional"))
      (node (ref "EXP") (pin "27") (pinfunction "27_27") (pintype "passive"))
    )
    (net (code "24") (name "28") (class "Default")
      (node (ref "ARM") (pin "18") (pinfunction "U2TX/PG1_18") (pintype "bidirectional"))
      (node (ref "EXP") (pin "28") (pinfunction "28_28") (pintype "passive"))
      (node (ref "R2") (pin "1") (pinfunction "1_1") (pintype "passive"))
    )
    (net (code "25") (name "29") (class "Default")
      (node (ref "ARM") (pin "19") (pinfunction "U2RX/PG0_19") (pintype "bidirectional"))
      (node (ref "EXP") (pin "29") (pinfunction "29_29") (pintype "passive"))
      (node (ref "R1") (pin "1") (pinfunction "1_1") (pintype "passive"))
    )
    (net (code "26") (name "30") (class "Default")
      (node (ref "ARM") (pin "22") (pinfunction "C2-/PC7_22") (pintype "bidirectional"))
      (node (ref "EXP") (pin "30") (pinfunction "30_30") (pintype "passive"))
    )
    (net (code "27") (name "31") (class "Default")
      (node (ref "ARM") (pin "23") (pinfunction "C2+/C2O/PC6_23") (pintype "bidirectional"))
      (node (ref "EXP") (pin "31") (pinfunction "31_31") (pintype "passive"))
    )
    (net (code "28") (name "32") (class "Default")
      (node (ref "ARM") (pin "24") (pinfunction "C1+/C1O/PC5_24") (pintype "bidirectional"))
      (node (ref "EXP") (pin "32") (pinfunction "32_32") (pintype "passive"))
    )
    (net (code "29") (name "33") (class "Default")
      (node (ref "ARM") (pin "25") (pinfunction "CCP5/PC4_25") (pintype "bidirectional"))
      (node (ref "EXP") (pin "33") (pinfunction "33_33") (pintype "passive"))
    )
    (net (code "30") (name "AGND") (class "Default")
      (node (ref "C10") (pin "2") (pinfunction "2_2") (pintype "passive"))
      (node (ref "C11") (pin "2") (pinfunction "2_2") (pintype "passive"))
      (node (ref "C9") (pin "1") (pinfunction "1_1") (pintype "passive"))
      (node (ref "U3") (pin "2") (pinfunction "GND_2") (pintype "power_in"))
      (node (ref "VS") (pin "37") (pinfunction "AGND0_37") (pintype "power_in"))
      (node (ref "VS") (pin "40") (pinfunction "AGND1_40") (pintype "power_in"))
      (node (ref "VS") (pin "41") (pinfunction "AGND2_41") (pintype "power_in"))
      (node (ref "VS") (pin "47") (pinfunction "AGND3_47") (pintype "power_in"))
      (node (ref "VS_C14") (pin "2") (pinfunction "2_2") (pintype "passive"))
      (node (ref "VS_C15") (pin "2") (pinfunction "2_2") (pintype "passive"))
      (node (ref "VS_C3") (pin "1") (pinfunction "1_1") (pintype "passive"))
      (node (ref "VS_C4") (pin "1") (pinfunction "1_1") (pintype "passive"))
      (node (ref "VS_C5") (pin "1") (pinfunction "1_1") (pintype "passive"))
      (node (ref "VS_C6") (pin "1") (pinfunction "1_1") (pintype "passive"))
      (node (ref "VS_CL2") (pin "2") (pinfunction "2_2") (pintype "passive"))
      (node (ref "VS_CR2") (pin "2") (pinfunction "2_2") (pintype "passive"))
      (node (ref "VS_GND") (pin "2") (pinfunction "2_2") (pintype "passive"))
      (node (ref "VS_R7") (pin "2") (pinfunction "2_2") (pintype "passive"))
      (node (ref "VS_R8") (pin "2") (pinfunction "2_2") (pintype "passive"))
    )
    (net (code "31") (name "FM_CS") (class "Default")
      (node (ref "ARM") (pin "73") (pinfunction "SSI1FSS/PE1_73") (pintype "bidirectional"))
      (node (ref "FM") (pin "1") (pinfunction "-CS_1") (pintype "input"))
      (node (ref "FM_R1") (pin "1") (pinfunction "1_1") (pintype "passive"))
    )
    (net (code "32") (name "GND") (class "Default")
      (node (ref "ARM") (pin "15") (pinfunction "GND_15") (pintype "power_in"))
      (node (ref "ARM") (pin "21") (pinfunction "GND_21") (pintype "power_in"))
      (node (ref "ARM") (pin "33") (pinfunction "GND_33") (pintype "power_in"))
      (node (ref "ARM") (pin "39") (pinfunction "GND_39") (pintype "power_in"))
      (node (ref "ARM") (pin "4") (pinfunction "GNDA_4") (pintype "power_in"))
      (node (ref "ARM") (pin "42") (pinfunction "GNDPHY_42") (pintype "power_in"))
      (node (ref "ARM") (pin "45") (pinfunction "GND_45") (pintype "power_in"))
      (node (ref "ARM") (pin "50") (pinfunction "~{WAKE}_50") (pintype "input"))
      (node (ref "ARM") (pin "54") (pinfunction "GND_54") (pintype "power_in"))
      (node (ref "ARM") (pin "57") (pinfunction "GND_57") (pintype "power_in"))
      (node (ref "ARM") (pin "63") (pinfunction "GND_63") (pintype "power_in"))
      (node (ref "ARM") (pin "65") (pinfunction "CMOD0_65") (pintype "bidirectional"))
      (node (ref "ARM") (pin "69") (pinfunction "GND_69") (pintype "power_in"))
      (node (ref "ARM") (pin "76") (pinfunction "CMOD1_76") (pintype "bidirectional"))
      (node (ref "ARM") (pin "82") (pinfunction "GND_82") (pintype "power_in"))
      (node (ref "ARM") (pin "85") (pinfunction "GNDPHY_85") (pintype "power_in"))
      (node (ref "ARM") (pin "86") (pinfunction "GNDPHY_86") (pintype "power_in"))
      (node (ref "ARM") (pin "87") (pinfunction "GND_87") (pintype "power_in"))
      (node (ref "ARM") (pin "9") (pinfunction "GND_9") (pintype "power_in"))
      (node (ref "ARM") (pin "94") (pinfunction "GND_94") (pintype "power_in"))
      (node (ref "ARM") (pin "97") (pinfunction "GNDA_97") (pintype "power_in"))
      (node (ref "ARM_C1") (pin "2") (pinfunction "2_2") (pintype "passive"))
      (node (ref "ARM_C10") (pin "2") (pinfunction "2_2") (pintype "passive"))
      (node (ref "ARM_C11") (pin "2") (pinfunction "2_2") (pintype "passive"))
      (node (ref "ARM_C12") (pin "2") (pinfunction "2_2") (pintype "passive"))
      (node (ref "ARM_C2") (pin "2") (pinfunction "2_2") (pintype "passive"))
      (node (ref "ARM_C3") (pin "2") (pinfunction "2_2") (pintype "passive"))
      (node (ref "ARM_C4") (pin "2") (pinfunction "2_2") (pintype "passive"))
      (node (ref "ARM_C5") (pin "2") (pinfunction "2_2") (pintype "passive"))
      (node (ref "ARM_C6") (pin "2") (pinfunction "2_2") (pintype "passive"))
      (node (ref "ARM_C7") (pin "2") (pinfunction "2_2") (pintype "passive"))
      (node (ref "ARM_C8") (pin "2") (pinfunction "2_2") (pintype "passive"))
      (node (ref "ARM_C9") (pin "2") (pinfunction "2_2") (pintype "passive"))
      (node (ref "ARM_R4") (pin "2") (pinfunction "2_2") (pintype "passive"))
      (node (ref "C1") (pin "-") (pinfunction "-_-") (pintype "passive"))
      (node (ref "C12") (pin "1") (pinfunction "1_1") (pintype "passive"))
      (node (ref "C13") (pin "2") (pinfunction "2_2") (pintype "passive"))
      (node (ref "C14") (pin "2") (pinfunction "2_2") (pintype "passive"))
      (node (ref "C2") (pin "2") (pinfunction "2_2") (pintype "passive"))
      (node (ref "C4") (pin "-") (pinfunction "-_-") (pintype "passive"))
      (node (ref "C5") (pin "2") (pinfunction "2_2") (pintype "passive"))
      (node (ref "C6") (pin "1") (pinfunction "1_1") (pintype "passive"))
      (node (ref "C7") (pin "2") (pinfunction "2_2") (pintype "passive"))
      (node (ref "C8") (pin "2") (pinfunction "2_2") (pintype "passive"))
      (node (ref "D1") (pin "A") (pinfunction "A_A") (pintype "passive"))
      (node (ref "EXP") (pin "1") (pinfunction "1_1") (pintype "passive"))
      (node (ref "EXP") (pin "2") (pinfunction "2_2") (pintype "passive"))
      (node (ref "EXP_C1") (pin "1") (pinfunction "1_1") (pintype "passive"))
      (node (ref "EXP_C2") (pin "1") (pinfunction "1_1") (pintype "passive"))
      (node (ref "EXT_PWR") (pin "1") (pinfunction "1_1") (pintype "passive"))
      (node (ref "EXT_PWR") (pin "2") (pinfunction "2_2") (pintype "passive"))
      (node (ref "FM") (pin "4") (pinfunction "GND_4") (pintype "power_in"))
      (node (ref "FM_C1") (pin "2") (pinfunction "2_2") (pintype "passive"))
      (node (ref "JTAG") (pin "10") (pinfunction "10_10") (pintype "passive"))
      (node (ref "JTAG") (pin "12") (pinfunction "12_12") (pintype "passive"))
      (node (ref "JTAG") (pin "14") (pinfunction "14_14") (pintype "passive"))
      (node (ref "JTAG") (pin "16") (pinfunction "16_16") (pintype "passive"))
      (node (ref "JTAG") (pin "18") (pinfunction "18_18") (pintype "passive"))
      (node (ref "JTAG") (pin "20") (pinfunction "20_20") (pintype "passive"))
      (node (ref "JTAG") (pin "4") (pinfunction "4_4") (pintype "passive"))
      (node (ref "JTAG") (pin "6") (pinfunction "6_6") (pintype "passive"))
      (node (ref "JTAG") (pin "8") (pinfunction "8_8") (pintype "passive"))
      (node (ref "POE") (pin "5") (pinfunction "RTN_5") (pintype "output"))
      (node (ref "PWR") (pin "3") (pinfunction "3_3") (pintype "passive"))
      (node (ref "PWR") (pin "4") (pinfunction "4_4") (pintype "passive"))
      (node (ref "PWR_C1") (pin "1") (pinfunction "1_1") (pintype "passive"))
      (node (ref "PWR_C2") (pin "1") (pinfunction "1_1") (pintype "passive"))
      (node (ref "RJ_C1") (pin "2") (pinfunction "2_2") (pintype "passive"))
      (node (ref "RJ_C10") (pin "2") (pinfunction "2_2") (pintype "passive"))
      (node (ref "RJ_C2") (pin "1") (pinfunction "1_1") (pintype "passive"))
      (node (ref "RJ_C3") (pin "1") (pinfunction "1_1") (pintype "passive"))
      (node (ref "RJ_C4") (pin "1") (pinfunction "1_1") (pintype "passive"))
      (node (ref "RJ_C5") (pin "1") (pinfunction "1_1") (pintype "passive"))
      (node (ref "RJ_C6") (pin "1") (pinfunction "1_1") (pintype "passive"))
      (node (ref "RJ_C7") (pin "1") (pinfunction "1_1") (pintype "passive"))
      (node (ref "RJ_C8") (pin "1") (pinfunction "1_1") (pintype "passive"))
      (node (ref "RJ_C9") (pin "1") (pinfunction "1_1") (pintype "passive"))
      (node (ref "SD") (pin "6") (pinfunction "6_6") (pintype "bidirectional"))
      (node (ref "SD_C1") (pin "2") (pinfunction "2_2") (pintype "passive"))
      (node (ref "SD_C2") (pin "1") (pinfunction "1_1") (pintype "passive"))
      (node (ref "SD_C3") (pin "1") (pinfunction "1_1") (pintype "passive"))
      (node (ref "U1") (pin "3") (pinfunction "SGND_3") (pintype "power_in"))
      (node (ref "U1") (pin "6") (pinfunction "GND_6") (pintype "power_in"))
      (node (ref "U2") (pin "1") (pinfunction "GND_1") (pintype "passive"))
      (node (ref "U4") (pin "2") (pinfunction "GND_2") (pintype "power_in"))
      (node (ref "UART2") (pin "1") (pinfunction "1_1") (pintype "passive"))
      (node (ref "USB") (pin "GND") (pinfunction "GND_GND") (pintype "bidirectional"))
      (node (ref "USB_C1") (pin "1") (pinfunction "1_1") (pintype "passive"))
      (node (ref "USB_C2") (pin "2") (pinfunction "2_2") (pintype "passive"))
      (node (ref "USB_C3") (pin "2") (pinfunction "2_2") (pintype "passive"))
      (node (ref "USB_C4") (pin "1") (pinfunction "1_1") (pintype "passive"))
      (node (ref "VS") (pin "16") (pinfunction "GND1_16") (pintype "power_in"))
      (node (ref "VS") (pin "20") (pinfunction "GND2_20") (pintype "power_in"))
      (node (ref "VS") (pin "21") (pinfunction "GND3_21") (pintype "power_in"))
      (node (ref "VS") (pin "22") (pinfunction "GND4_22") (pintype "power_in"))
      (node (ref "VS") (pin "35") (pinfunction "GND5_35") (pintype "power_in"))
      (node (ref "VS") (pin "4") (pinfunction "GND0_4") (pintype "power_in"))
      (node (ref "VS_C1") (pin "2") (pinfunction "2_2") (pintype "passive"))
      (node (ref "VS_C10") (pin "2") (pinfunction "2_2") (pintype "passive"))
      (node (ref "VS_C11") (pin "2") (pinfunction "2_2") (pintype "passive"))
      (node (ref "VS_C12") (pin "2") (pinfunction "2_2") (pintype "passive"))
      (node (ref "VS_C13") (pin "2") (pinfunction "2_2") (pintype "passive"))
      (node (ref "VS_C2") (pin "2") (pinfunction "2_2") (pintype "passive"))
      (node (ref "VS_C7") (pin "2") (pinfunction "2_2") (pintype "passive"))
      (node (ref "VS_C8") (pin "2") (pinfunction "2_2") (pintype "passive"))
      (node (ref "VS_C9") (pin "2") (pinfunction "2_2") (pintype "passive"))
      (node (ref "VS_R10") (pin "2") (pinfunction "2_2") (pintype "passive"))
      (node (ref "VS_R11") (pin "2") (pinfunction "2_2") (pintype "passive"))
      (node (ref "VS_R12") (pin "2") (pinfunction "2_2") (pintype "passive"))
      (node (ref "VS_R2") (pin "1") (pinfunction "1_1") (pintype "passive"))
      (node (ref "VS_R3") (pin "1") (pinfunction "1_1") (pintype "passive"))
      (node (ref "VS_R9") (pin "2") (pinfunction "2_2") (pintype "passive"))
    )
    (net (code "33") (name "I2S_LROUT") (class "Default")
      (node (ref "I2S") (pin "1") (pinfunction "1_1") (pintype "passive"))
      (node (ref "VS") (pin "36") (pinfunction "GPIO4_36") (pintype "bidirectional"))
      (node (ref "VS_R9") (pin "1") (pinfunction "1_1") (pintype "passive"))
    )
    (net (code "34") (name "I2S_MCLK") (class "Default")
      (node (ref "I2S") (pin "2") (pinfunction "2_2") (pintype "passive"))
      (node (ref "VS") (pin "25") (pinfunction "GPIO5_25") (pintype "bidirectional"))
      (node (ref "VS_R10") (pin "1") (pinfunction "1_1") (pintype "passive"))
    )
    (net (code "35") (name "I2S_SCLK") (class "Default")
      (node (ref "I2S") (pin "3") (pinfunction "3_3") (pintype "passive"))
      (node (ref "VS") (pin "11") (pinfunction "GPIO6_11") (pintype "bidirectional"))
      (node (ref "VS_R11") (pin "1") (pinfunction "1_1") (pintype "passive"))
    )
    (net (code "36") (name "I2S_SDATA") (class "Default")
      (node (ref "I2S") (pin "4") (pinfunction "4_4") (pintype "passive"))
      (node (ref "VS") (pin "12") (pinfunction "GPIO7_12") (pintype "bidirectional"))
      (node (ref "VS_R12") (pin "1") (pinfunction "1_1") (pintype "passive"))
    )
    (net (code "37") (name "LED1") (class "Default")
      (node (ref "ARM") (pin "59") (pinfunction "LED0/PF3_59") (pintype "bidirectional"))
      (node (ref "RJ_R5") (pin "2") (pinfunction "2_2") (pintype "passive"))
    )
    (net (code "38") (name "LED2") (class "Default")
      (node (ref "ARM") (pin "60") (pinfunction "LED1/PF2_60") (pintype "bidirectional"))
      (node (ref "RJ_R6") (pin "2") (pinfunction "2_2") (pintype "passive"))
    )
    (net (code "39") (name "NC") (class "Default")
      (node (ref "RJ") (pin "8") (pinfunction "NC_8") (pintype "power_in"))
    )
    (net (code "40") (name "NC_GND(TAIMAG)") (class "Default")
      (node (ref "RJ") (pin "7") (pinfunction "NC_GND(TAIMAG)_7") (pintype "power_in"))
    )
    (net (code "41") (name "Net-(ARM-ERBIAS)") (class "Default")
      (node (ref "ARM") (pin "41") (pinfunction "ERBIAS_41") (pintype "power_in"))
      (node (ref "ARM_R4") (pin "1") (pinfunction "1_1") (pintype "passive"))
    )
    (net (code "42") (name "Net-(ARM-MDIO)") (class "Default")
      (node (ref "ARM") (pin "58") (pinfunction "MDIO_58") (pintype "bidirectional"))
      (node (ref "ARM_R3") (pin "1") (pinfunction "1_1") (pintype "passive"))
    )
    (net (code "43") (name "Net-(ARM-OSC0)") (class "Default")
      (node (ref "ARM") (pin "48") (pinfunction "OSC0_48") (pintype "bidirectional"))
      (node (ref "ARM_C1") (pin "1") (pinfunction "1_1") (pintype "passive"))
      (node (ref "ARM_Q1") (pin "2") (pinfunction "2_2") (pintype "passive"))
    )
    (net (code "44") (name "Net-(ARM-OSC1)") (class "Default")
      (node (ref "ARM") (pin "49") (pinfunction "OSC1_49") (pintype "bidirectional"))
      (node (ref "ARM_C2") (pin "1") (pinfunction "1_1") (pintype "passive"))
      (node (ref "ARM_Q1") (pin "1") (pinfunction "1_1") (pintype "passive"))
    )
    (net (code "45") (name "Net-(ARM-XTALNPHY)") (class "Default")
      (node (ref "ARM") (pin "17") (pinfunction "XTALNPHY_17") (pintype "bidirectional"))
      (node (ref "ARM_C4") (pin "1") (pinfunction "1_1") (pintype "passive"))
      (node (ref "ARM_Q2") (pin "1") (pinfunction "1_1") (pintype "passive"))
    )
    (net (code "46") (name "Net-(ARM-XTALPPHY)") (class "Default")
      (node (ref "ARM") (pin "16") (pinfunction "XTALPPHY_16") (pintype "bidirectional"))
      (node (ref "ARM_C3") (pin "1") (pinfunction "1_1") (pintype "passive"))
      (node (ref "ARM_Q2") (pin "2") (pinfunction "2_2") (pintype "passive"))
    )
    (net (code "47") (name "Net-(ARM-~{RESET})") (class "Default")
      (node (ref "ARM") (pin "64") (pinfunction "~{RESET}_64") (pintype "input"))
      (node (ref "ARM_R1") (pin "2") (pinfunction "2_2") (pintype "passive"))
    )
    (net (code "48") (name "Net-(D2-PadA)") (class "Default")
      (node (ref "D2") (pin "A") (pinfunction "A_A") (pintype "passive"))
      (node (ref "EXT_PWR") (pin "3") (pinfunction "3_3") (pintype "passive"))
    )
    (net (code "49") (name "Net-(D2-PadC)") (class "Default")
      (node (ref "D2") (pin "C") (pinfunction "C_C") (pintype "passive"))
      (node (ref "D3") (pin "C") (pinfunction "C_C") (pintype "passive"))
      (node (ref "FUSE") (pin "1") (pinfunction "1_1") (pintype "passive"))
    )
    (net (code "50") (name "Net-(OUT-Pad1)") (class "Default")
      (node (ref "OUT") (pin "1") (pinfunction "1_1") (pintype "passive"))
      (node (ref "VS_GBUF") (pin "2") (pinfunction "2_2") (pintype "passive"))
      (node (ref "VS_GND") (pin "1") (pinfunction "1_1") (pintype "passive"))
    )
    (net (code "51") (name "Net-(OUT-Pad2)") (class "Default")
      (node (ref "OUT") (pin "2") (pinfunction "2_2") (pintype "passive"))
      (node (ref "OUT") (pin "4") (pinfunction "4_4") (pintype "passive"))
      (node (ref "VS_CL") (pin "2") (pinfunction "2_2") (pintype "passive"))
      (node (ref "VS_R8") (pin "1") (pinfunction "1_1") (pintype "passive"))
    )
    (net (code "52") (name "Net-(OUT-Pad3)") (class "Default")
      (node (ref "OUT") (pin "3") (pinfunction "3_3") (pintype "passive"))
      (node (ref "OUT") (pin "5") (pinfunction "5_5") (pintype "passive"))
      (node (ref "VS_CR") (pin "2") (pinfunction "2_2") (pintype "passive"))
      (node (ref "VS_R7") (pin "1") (pinfunction "1_1") (pintype "passive"))
    )
    (net (code "53") (name "Net-(POE-CLASS)") (class "Default")
      (node (ref "POE") (pin "2") (pinfunction "CLASS_2") (pintype "output"))
      (node (ref "POE_CLA") (pin "2") (pinfunction "2_2") (pintype "passive"))
    )
    (net (code "54") (name "Net-(POE-DET)") (class "Default")
      (node (ref "POE") (pin "3") (pinfunction "DET_3") (pintype "output"))
      (node (ref "POE_DET") (pin "2") (pinfunction "2_2") (pintype "passive"))
    )
    (net (code "55") (name "Net-(POE-ILM)") (class "Default")
      (node (ref "POE") (pin "1") (pinfunction "ILM_1") (pintype "output"))
      (node (ref "POE_ILM") (pin "2") (pinfunction "2_2") (pintype "passive"))
    )
    (net (code "56") (name "Net-(POE-POE-)") (class "Default")
      (node (ref "POE") (pin "4") (pinfunction "POE-_4") (pintype "power_in"))
      (node (ref "POE_C1") (pin "2") (pinfunction "2_2") (pintype "passive"))
      (node (ref "POE_CLA") (pin "1") (pinfunction "1_1") (pintype "passive"))
      (node (ref "POE_D1") (pin "A") (pinfunction "A_A") (pintype "passive"))
      (node (ref "POE_ILM") (pin "1") (pinfunction "1_1") (pintype "passive"))
      (node (ref "RJ") (pin "10") (pinfunction "POE-_10") (pintype "power_in"))
    )
    (net (code "57") (name "Net-(R1-Pad2)") (class "Default")
      (node (ref "R1") (pin "2") (pinfunction "2_2") (pintype "passive"))
      (node (ref "UART2") (pin "4") (pinfunction "4_4") (pintype "passive"))
    )
    (net (code "58") (name "Net-(R2-Pad2)") (class "Default")
      (node (ref "R2") (pin "2") (pinfunction "2_2") (pintype "passive"))
      (node (ref "UART2") (pin "5") (pinfunction "5_5") (pintype "passive"))
    )
    (net (code "59") (name "Net-(RJ-PadLED1-)") (class "Default")
      (node (ref "RJ") (pin "LED1-") (pinfunction "LED1-_LED1-") (pintype "input"))
      (node (ref "RJ_R5") (pin "1") (pinfunction "1_1") (pintype "passive"))
    )
    (net (code "60") (name "Net-(RJ-PadLED2-)") (class "Default")
      (node (ref "RJ") (pin "LED2-") (pinfunction "LED2-_LED2-") (pintype "input"))
      (node (ref "RJ_R6") (pin "1") (pinfunction "1_1") (pintype "passive"))
    )
    (net (code "61") (name "Net-(RJ-SHIELD-PadNC0)") (class "Default")
      (node (ref "RJ") (pin "NC0") (pinfunction "SHIELD_NC0") (pintype "power_in"))
      (node (ref "RJ") (pin "NC1") (pinfunction "SHIELD_NC1") (pintype "power_in"))
      (node (ref "RJ_R7") (pin "2") (pinfunction "2_2") (pintype "passive"))
    )
    (net (code "62") (name "Net-(RJ_C10-Pad1)") (class "Default")
      (node (ref "RJ_C10") (pin "1") (pinfunction "1_1") (pintype "passive"))
      (node (ref "RJ_R7") (pin "1") (pinfunction "1_1") (pintype "passive"))
    )
    (net (code "63") (name "Net-(SD-Pad1)") (class "Default")
      (node (ref "SD") (pin "1") (pinfunction "1_1") (pintype "bidirectional"))
      (node (ref "SD_R5") (pin "2") (pinfunction "2_2") (pintype "passive"))
    )
    (net (code "64") (name "Net-(SD-Pad8)") (class "Default")
      (node (ref "SD") (pin "8") (pinfunction "8_8") (pintype "bidirectional"))
      (node (ref "SD_R2") (pin "2") (pinfunction "2_2") (pintype "passive"))
    )
    (net (code "65") (name "Net-(SD_Q1-D)") (class "Default")
      (node (ref "SD") (pin "4") (pinfunction "4_4") (pintype "bidirectional"))
      (node (ref "SD_C1") (pin "1") (pinfunction "1_1") (pintype "passive"))
      (node (ref "SD_Q1") (pin "3") (pinfunction "D_3") (pintype "passive"))
      (node (ref "SD_R2") (pin "1") (pinfunction "1_1") (pintype "passive"))
      (node (ref "SD_R3") (pin "1") (pinfunction "1_1") (pintype "passive"))
      (node (ref "SD_R4") (pin "1") (pinfunction "1_1") (pintype "passive"))
      (node (ref "SD_R5") (pin "1") (pinfunction "1_1") (pintype "passive"))
    )
    (net (code "66") (name "Net-(U1-BST)") (class "Default")
      (node (ref "C3") (pin "1") (pinfunction "1_1") (pintype "passive"))
      (node (ref "U1") (pin "1") (pinfunction "BST_1") (pintype "power_in"))
    )
    (net (code "67") (name "Net-(U1-OUT)") (class "Default")
      (node (ref "C3") (pin "2") (pinfunction "2_2") (pintype "passive"))
      (node (ref "D1") (pin "C") (pinfunction "C_C") (pintype "passive"))
      (node (ref "L1") (pin "1") (pinfunction "1_1") (pintype "passive"))
      (node (ref "U1") (pin "8") (pinfunction "OUT_8") (pintype "power_in"))
    )
    (net (code "68") (name "Net-(U1-VD)") (class "Default")
      (node (ref "C2") (pin "1") (pinfunction "1_1") (pintype "passive"))
      (node (ref "U1") (pin "2") (pinfunction "VD_2") (pintype "input"))
    )
    (net (code "69") (name "Net-(U3-BYPASS)") (class "Default")
      (node (ref "C10") (pin "1") (pinfunction "1_1") (pintype "passive"))
      (node (ref "U3") (pin "4") (pinfunction "BYPASS_4") (pintype "input"))
    )
    (net (code "70") (name "Net-(U3-ON-~{OFF})") (class "Default")
      (node (ref "C9") (pin "2") (pinfunction "2_2") (pintype "passive"))
      (node (ref "L2") (pin "2") (pinfunction "2_2") (pintype "passive"))
      (node (ref "U3") (pin "1") (pinfunction "VIN_1") (pintype "power_in"))
      (node (ref "U3") (pin "3") (pinfunction "ON-~{OFF}_3") (pintype "input"))
    )
    (net (code "71") (name "Net-(U4-BYPASS)") (class "Default")
      (node (ref "C13") (pin "1") (pinfunction "1_1") (pintype "passive"))
      (node (ref "U4") (pin "4") (pinfunction "BYPASS_4") (pintype "input"))
    )
    (net (code "72") (name "Net-(USB_Q1-D)") (class "Default")
      (node (ref "USB") (pin "VBUS") (pinfunction "VBUS_VBUS") (pintype "bidirectional"))
      (node (ref "USB_C2") (pin "1") (pinfunction "1_1") (pintype "passive"))
      (node (ref "USB_C3") (pin "1") (pinfunction "1_1") (pintype "passive"))
      (node (ref "USB_Q1") (pin "3") (pinfunction "D_3") (pintype "passive"))
    )
    (net (code "73") (name "Net-(USB_Q1-G)") (class "Default")
      (node (ref "USB_C1") (pin "2") (pinfunction "2_2") (pintype "passive"))
      (node (ref "USB_Q1") (pin "1") (pinfunction "G_1") (pintype "passive"))
      (node (ref "USB_R1") (pin "2") (pinfunction "2_2") (pintype "passive"))
      (node (ref "USB_R2") (pin "1") (pinfunction "1_1") (pintype "passive"))
    )
    (net (code "74") (name "Net-(USB_Q1-S)") (class "Default")
      (node (ref "USB_C4") (pin "2") (pinfunction "2_2") (pintype "passive"))
      (node (ref "USB_L1") (pin "2") (pinfunction "2_2") (pintype "passive"))
      (node (ref "USB_Q1") (pin "2") (pinfunction "S_2") (pintype "passive"))
      (node (ref "USB_R1") (pin "1") (pinfunction "1_1") (pintype "passive"))
    )
    (net (code "75") (name "Net-(VS-GBUF)") (class "Default")
      (node (ref "VS") (pin "42") (pinfunction "GBUF_42") (pintype "passive"))
      (node (ref "VS_GBUF") (pin "1") (pinfunction "1_1") (pintype "passive"))
      (node (ref "VS_R6") (pin "2") (pinfunction "2_2") (pintype "passive"))
    )
    (net (code "76") (name "Net-(VS-GPIO0)") (class "Default")
      (node (ref "VS") (pin "33") (pinfunction "GPIO0_33") (pintype "bidirectional"))
      (node (ref "VS") (pin "34") (pinfunction "GPIO1_34") (pintype "bidirectional"))
      (node (ref "VS_R3") (pin "2") (pinfunction "2_2") (pintype "passive"))
    )
    (net (code "77") (name "Net-(VS-GPIO2)") (class "Default")
      (node (ref "VS") (pin "10") (pinfunction "GPIO3_10") (pintype "bidirectional"))
      (node (ref "VS") (pin "9") (pinfunction "GPIO2_9") (pintype "bidirectional"))
      (node (ref "VS_R2") (pin "2") (pinfunction "2_2") (pintype "passive"))
    )
    (net (code "78") (name "Net-(VS-LEFT)") (class "Default")
      (node (ref "VS") (pin "46") (pinfunction "LEFT_46") (pintype "passive"))
      (node (ref "VS_R4") (pin "2") (pinfunction "2_2") (pintype "passive"))
      (node (ref "VS_RL") (pin "1") (pinfunction "1_1") (pintype "passive"))
    )
    (net (code "79") (name "Net-(VS-RCAP)") (class "Default")
      (node (ref "VS") (pin "44") (pinfunction "RCAP_44") (pintype "passive"))
      (node (ref "VS_C6") (pin "2") (pinfunction "2_2") (pintype "passive"))
    )
    (net (code "80") (name "Net-(VS-RIGHT)") (class "Default")
      (node (ref "VS") (pin "39") (pinfunction "RIGHT_39") (pintype "passive"))
      (node (ref "VS_R5") (pin "2") (pinfunction "2_2") (pintype "passive"))
      (node (ref "VS_RR") (pin "1") (pinfunction "1_1") (pintype "passive"))
    )
    (net (code "81") (name "Net-(VS-XTALI)") (class "Default")
      (node (ref "VS") (pin "18") (pinfunction "XTALI_18") (pintype "passive"))
      (node (ref "VS_C2") (pin "1") (pinfunction "1_1") (pintype "passive"))
      (node (ref "VS_Q1") (pin "1") (pinfunction "1_1") (pintype "passive"))
      (node (ref "VS_R1") (pin "2") (pinfunction "2_2") (pintype "passive"))
    )
    (net (code "82") (name "Net-(VS-XTALO)") (class "Default")
      (node (ref "VS") (pin "17") (pinfunction "XTALO_17") (pintype "passive"))
      (node (ref "VS_C1") (pin "1") (pinfunction "1_1") (pintype "passive"))
      (node (ref "VS_Q1") (pin "2") (pinfunction "2_2") (pintype "passive"))
      (node (ref "VS_R1") (pin "1") (pinfunction "1_1") (pintype "passive"))
    )
    (net (code "83") (name "Net-(VS_C3-Pad2)") (class "Default")
      (node (ref "VS_C3") (pin "2") (pinfunction "2_2") (pintype "passive"))
      (node (ref "VS_R4") (pin "1") (pinfunction "1_1") (pintype "passive"))
    )
    (net (code "84") (name "Net-(VS_C4-Pad2)") (class "Default")
      (node (ref "VS_C4") (pin "2") (pinfunction "2_2") (pintype "passive"))
      (node (ref "VS_R5") (pin "1") (pinfunction "1_1") (pintype "passive"))
    )
    (net (code "85") (name "Net-(VS_C5-Pad2)") (class "Default")
      (node (ref "VS_C5") (pin "2") (pinfunction "2_2") (pintype "passive"))
      (node (ref "VS_R6") (pin "1") (pinfunction "1_1") (pintype "passive"))
    )
    (net (code "86") (name "Net-(VS_CL-Pad1)") (class "Default")
      (node (ref "VS_CL") (pin "1") (pinfunction "1_1") (pintype "passive"))
      (node (ref "VS_CL2") (pin "1") (pinfunction "1_1") (pintype "passive"))
      (node (ref "VS_RL") (pin "2") (pinfunction "2_2") (pintype "passive"))
    )
    (net (code "87") (name "Net-(VS_CR-Pad1)") (class "Default")
      (node (ref "VS_CR") (pin "1") (pinfunction "1_1") (pintype "passive"))
      (node (ref "VS_CR2") (pin "1") (pinfunction "1_1") (pintype "passive"))
      (node (ref "VS_RR") (pin "2") (pinfunction "2_2") (pintype "passive"))
    )
    (net (code "88") (name "POE+") (class "Default")
      (node (ref "D3") (pin "A") (pinfunction "A_A") (pintype "passive"))
      (node (ref "RJ") (pin "9") (pinfunction "POE+_9") (pintype "power_in"))
    )
    (net (code "89") (name "PWR+") (class "Default")
      (node (ref "C1") (pin "+") (pinfunction "+_+") (pintype "passive"))
      (node (ref "FUSE") (pin "2") (pinfunction "2_2") (pintype "passive"))
      (node (ref "POE") (pin "8") (pinfunction "POE+_8") (pintype "power_in"))
      (node (ref "POE_C1") (pin "1") (pinfunction "1_1") (pintype "passive"))
      (node (ref "POE_D1") (pin "C") (pinfunction "C_C") (pintype "passive"))
      (node (ref "POE_DET") (pin "1") (pinfunction "1_1") (pintype "passive"))
      (node (ref "U1") (pin "5") (pinfunction "ON/~{OFF}_5") (pintype "input"))
      (node (ref "U1") (pin "7") (pinfunction "VIN_7") (pintype "power_in"))
    )
    (net (code "90") (name "RD+") (class "Default")
      (node (ref "ARM") (pin "40") (pinfunction "RXIP_40") (pintype "bidirectional"))
      (node (ref "RJ") (pin "1") (pinfunction "RD+_1") (pintype "bidirectional"))
      (node (ref "RJ_C2") (pin "2") (pinfunction "2_2") (pintype "passive"))
      (node (ref "RJ_R1") (pin "1") (pinfunction "1_1") (pintype "passive"))
    )
    (net (code "91") (name "RD-") (class "Default")
      (node (ref "ARM") (pin "37") (pinfunction "RXIN_37") (pintype "bidirectional"))
      (node (ref "RJ") (pin "2") (pinfunction "RD-_2") (pintype "bidirectional"))
      (node (ref "RJ_C5") (pin "2") (pinfunction "2_2") (pintype "passive"))
      (node (ref "RJ_R2") (pin "1") (pinfunction "1_1") (pintype "passive"))
    )
    (net (code "92") (name "SCK") (class "Default")
      (node (ref "ARM") (pin "72") (pinfunction "SSI1CLK/PE0_72") (pintype "bidirectional"))
      (node (ref "EXP") (pin "10") (pinfunction "10_10") (pintype "passive"))
      (node (ref "FM") (pin "6") (pinfunction "CLK_6") (pintype "input"))
      (node (ref "SD") (pin "5") (pinfunction "5_5") (pintype "bidirectional"))
    )
    (net (code "93") (name "SD_CS") (class "Default")
      (node (ref "ARM") (pin "67") (pinfunction "PWM3/PB1_67") (pintype "bidirectional"))
      (node (ref "SD") (pin "2") (pinfunction "2_2") (pintype "bidirectional"))
      (node (ref "SD_R4") (pin "2") (pinfunction "2_2") (pintype "passive"))
    )
    (net (code "94") (name "SD_PWR") (class "Default")
      (node (ref "ARM") (pin "66") (pinfunction "PWM2/PB0_66") (pintype "bidirectional"))
      (node (ref "SD_Q1") (pin "1") (pinfunction "G_1") (pintype "passive"))
      (node (ref "SD_R1") (pin "2") (pinfunction "2_2") (pintype "passive"))
    )
    (net (code "95") (name "SI") (class "Default")
      (node (ref "ARM") (pin "75") (pinfunction "SSI1TX/PE3_75") (pintype "bidirectional"))
      (node (ref "EXP") (pin "12") (pinfunction "12_12") (pintype "passive"))
      (node (ref "FM") (pin "5") (pinfunction "DI_5") (pintype "input"))
      (node (ref "SD") (pin "3") (pinfunction "3_3") (pintype "bidirectional"))
    )
    (net (code "96") (name "SO") (class "Default")
      (node (ref "ARM") (pin "74") (pinfunction "SSI1RX/PE2_74") (pintype "bidirectional"))
      (node (ref "EXP") (pin "11") (pinfunction "11_11") (pintype "passive"))
      (node (ref "FM") (pin "2") (pinfunction "DO_2") (pintype "output"))
      (node (ref "SD") (pin "7") (pinfunction "7_7") (pintype "bidirectional"))
      (node (ref "SD_R3") (pin "2") (pinfunction "2_2") (pintype "passive"))
    )
    (net (code "97") (name "TCK") (class "Default")
      (node (ref "ARM") (pin "80") (pinfunction "TCK/SWCLK/PC0_80") (pintype "bidirectional"))
      (node (ref "JTAG") (pin "9") (pinfunction "9_9") (pintype "passive"))
    )
    (net (code "98") (name "TD+") (class "Default")
      (node (ref "ARM") (pin "43") (pinfunction "TXOP_43") (pintype "bidirectional"))
      (node (ref "RJ") (pin "5") (pinfunction "TD+_5") (pintype "bidirectional"))
      (node (ref "RJ_C6") (pin "2") (pinfunction "2_2") (pintype "passive"))
      (node (ref "RJ_R3") (pin "1") (pinfunction "1_1") (pintype "passive"))
    )
    (net (code "99") (name "TD-") (class "Default")
      (node (ref "ARM") (pin "46") (pinfunction "TXON_46") (pintype "bidirectional"))
      (node (ref "RJ") (pin "6") (pinfunction "TD-_6") (pintype "bidirectional"))
      (node (ref "RJ_C9") (pin "2") (pinfunction "2_2") (pintype "passive"))
      (node (ref "RJ_R4") (pin "1") (pinfunction "1_1") (pintype "passive"))
    )
    (net (code "100") (name "TDI") (class "Default")
      (node (ref "ARM") (pin "78") (pinfunction "TDI/PC2_78") (pintype "bidirectional"))
      (node (ref "JTAG") (pin "5") (pinfunction "5_5") (pintype "passive"))
    )
    (net (code "101") (name "TDO") (class "Default")
      (node (ref "ARM") (pin "77") (pinfunction "TDO/SWO/PC3_77") (pintype "bidirectional"))
      (node (ref "JTAG") (pin "13") (pinfunction "13_13") (pintype "passive"))
    )
    (net (code "102") (name "TMS") (class "Default")
      (node (ref "ARM") (pin "79") (pinfunction "TMS/SWDIO/PC1_79") (pintype "bidirectional"))
      (node (ref "JTAG") (pin "7") (pinfunction "7_7") (pintype "passive"))
    )
    (net (code "103") (name "TRST") (class "Default")
      (node (ref "ARM") (pin "89") (pinfunction "TRST/PB7_89") (pintype "bidirectional"))
      (node (ref "ARM_R2") (pin "1") (pinfunction "1_1") (pintype "passive"))
      (node (ref "JTAG") (pin "3") (pinfunction "3_3") (pintype "passive"))
    )
    (net (code "104") (name "USB_PWR") (class "Default")
      (node (ref "ARM") (pin "61") (pinfunction "PWM1/PF1_61") (pintype "bidirectional"))
      (node (ref "USB_R2") (pin "2") (pinfunction "2_2") (pintype "passive"))
    )
    (net (code "105") (name "VBAT") (class "Default")
      (node (ref "ARM") (pin "55") (pinfunction "VBAT_55") (pintype "power_in"))
    )
    (net (code "106") (name "VS_CS") (class "Default")
      (node (ref "ARM") (pin "34") (pinfunction "CCP1/PA6_34") (pintype "bidirectional"))
      (node (ref "VS") (pin "23") (pinfunction "~{CS}_23") (pintype "input"))
    )
    (net (code "107") (name "VS_DCS") (class "Default")
      (node (ref "ARM") (pin "29") (pinfunction "SSI0FSS/PA3_29") (pintype "bidirectional"))
      (node (ref "VS") (pin "13") (pinfunction "~{DCS}_13") (pintype "input"))
    )
    (net (code "108") (name "VS_DREQ") (class "Default")
      (node (ref "ARM") (pin "27") (pinfunction "U0TX/PA1_27") (pintype "bidirectional"))
      (node (ref "VS") (pin "8") (pinfunction "~{DREQ}_8") (pintype "input"))
    )
    (net (code "109") (name "VS_RST") (class "Default")
      (node (ref "ARM") (pin "35") (pinfunction "CCP4/PA7_35") (pintype "bidirectional"))
      (node (ref "VS") (pin "3") (pinfunction "~{RESET}_3") (pintype "input"))
    )
    (net (code "110") (name "VS_SCK") (class "Default")
      (node (ref "ARM") (pin "28") (pinfunction "SSI0CLK/PA2_28") (pintype "bidirectional"))
      (node (ref "VS") (pin "28") (pinfunction "SCLK_28") (pintype "input"))
    )
    (net (code "111") (name "VS_SI") (class "Default")
      (node (ref "ARM") (pin "31") (pinfunction "SSI0TX/PA5_31") (pintype "bidirectional"))
      (node (ref "VS") (pin "29") (pinfunction "SI_29") (pintype "input"))
    )
    (net (code "112") (name "VS_SO") (class "Default")
      (node (ref "ARM") (pin "30") (pinfunction "SSI0RX/PA4_30") (pintype "bidirectional"))
      (node (ref "VS") (pin "30") (pinfunction "SO_30") (pintype "output"))
    )
    (net (code "113") (name "unconnected-(ARM-U0RX{slash}PA0-Pad26)") (class "Default")
      (node (ref "ARM") (pin "26") (pinfunction "U0RX/PA0_26") (pintype "bidirectional"))
    )
    (net (code "114") (name "unconnected-(ARM-XOSC0-Pad52)") (class "Default")
      (node (ref "ARM") (pin "52") (pinfunction "XOSC0_52") (pintype "bidirectional"))
    )
    (net (code "115") (name "unconnected-(ARM-XOSC1-Pad53)") (class "Default")
      (node (ref "ARM") (pin "53") (pinfunction "XOSC1_53") (pintype "bidirectional"))
    )
    (net (code "116") (name "unconnected-(ARM-~{HIB}-Pad51)") (class "Default")
      (node (ref "ARM") (pin "51") (pinfunction "~{HIB}_51") (pintype "output"))
    )
    (net (code "117") (name "unconnected-(EXP-Pad34)") (class "Default")
      (node (ref "EXP") (pin "34") (pinfunction "34_34") (pintype "passive"))
    )
    (net (code "118") (name "unconnected-(JTAG-Pad2)") (class "Default")
      (node (ref "JTAG") (pin "2") (pinfunction "2_2") (pintype "passive"))
    )
    (net (code "119") (name "unconnected-(JTAG-Pad11)") (class "Default")
      (node (ref "JTAG") (pin "11") (pinfunction "11_11") (pintype "passive"))
    )
    (net (code "120") (name "unconnected-(JTAG-Pad15)") (class "Default")
      (node (ref "JTAG") (pin "15") (pinfunction "15_15") (pintype "passive"))
    )
    (net (code "121") (name "unconnected-(JTAG-Pad17)") (class "Default")
      (node (ref "JTAG") (pin "17") (pinfunction "17_17") (pintype "passive"))
    )
    (net (code "122") (name "unconnected-(JTAG-Pad19)") (class "Default")
      (node (ref "JTAG") (pin "19") (pinfunction "19_19") (pintype "passive"))
    )
    (net (code "123") (name "unconnected-(POE-PG-Pad6)") (class "Default")
      (node (ref "POE") (pin "6") (pinfunction "PG_6") (pintype "output"))
    )
    (net (code "124") (name "unconnected-(SD-SW1-PadK1)") (class "Default")
      (node (ref "SD") (pin "K1") (pinfunction "SW1_K1") (pintype "bidirectional"))
    )
    (net (code "125") (name "unconnected-(SD-SW2-PadK2)") (class "Default")
      (node (ref "SD") (pin "K2") (pinfunction "SW2_K2") (pintype "bidirectional"))
    )
    (net (code "126") (name "unconnected-(UART2-Pad2)") (class "Default")
      (node (ref "UART2") (pin "2") (pinfunction "2_2") (pintype "passive"))
    )
    (net (code "127") (name "unconnected-(UART2-Pad3)") (class "Default")
      (node (ref "UART2") (pin "3") (pinfunction "3_3") (pintype "passive"))
    )
    (net (code "128") (name "unconnected-(UART2-Pad6)") (class "Default")
      (node (ref "UART2") (pin "6") (pinfunction "6_6") (pintype "passive"))
    )
    (net (code "129") (name "unconnected-(USB-PadD+)") (class "Default")
      (node (ref "USB") (pin "D+") (pinfunction "D+_D+") (pintype "bidirectional"))
    )
    (net (code "130") (name "unconnected-(USB-PadD-)") (class "Default")
      (node (ref "USB") (pin "D-") (pinfunction "D-_D-") (pintype "bidirectional"))
    )
    (net (code "131") (name "unconnected-(VS-LINE2-Pad48)") (class "Default")
      (node (ref "VS") (pin "48") (pinfunction "LINE2_48") (pintype "passive"))
    )
    (net (code "132") (name "unconnected-(VS-MIC+{slash}LINE1-Pad1)") (class "Default")
      (node (ref "VS") (pin "1") (pinfunction "MIC+/LINE1_1") (pintype "passive"))
    )
    (net (code "133") (name "unconnected-(VS-MIC--Pad2)") (class "Default")
      (node (ref "VS") (pin "2") (pinfunction "MIC-_2") (pintype "passive"))
    )
    (net (code "134") (name "unconnected-(VS-TX-Pad27)") (class "Default")
      (node (ref "VS") (pin "27") (pinfunction "TX_27") (pintype "output"))
    )
    (net (code "135") (name "unconnected-(VS-VCO-Pad15)") (class "Default")
      (node (ref "VS") (pin "15") (pinfunction "VCO_15") (pintype "output"))
    )
    (net (code "136") (name "unconnected-(X1-Pad1)") (class "Default")
      (node (ref "X1") (pin "1") (pinfunction "1_1") (pintype "passive"))
    )
    (net (code "137") (name "unconnected-(X2-Pad1)") (class "Default")
      (node (ref "X2") (pin "1") (pinfunction "1_1") (pintype "passive"))
    )
    (net (code "138") (name "unconnected-(X3-Pad1)") (class "Default")
      (node (ref "X3") (pin "1") (pinfunction "1_1") (pintype "passive"))
    )
    (net (code "139") (name "unconnected-(X4-Pad1)") (class "Default")
      (node (ref "X4") (pin "1") (pinfunction "1_1") (pintype "passive"))
    )
  )
)
